# lora.net
KiCad netlist of a schematic drawn in Altium Designer
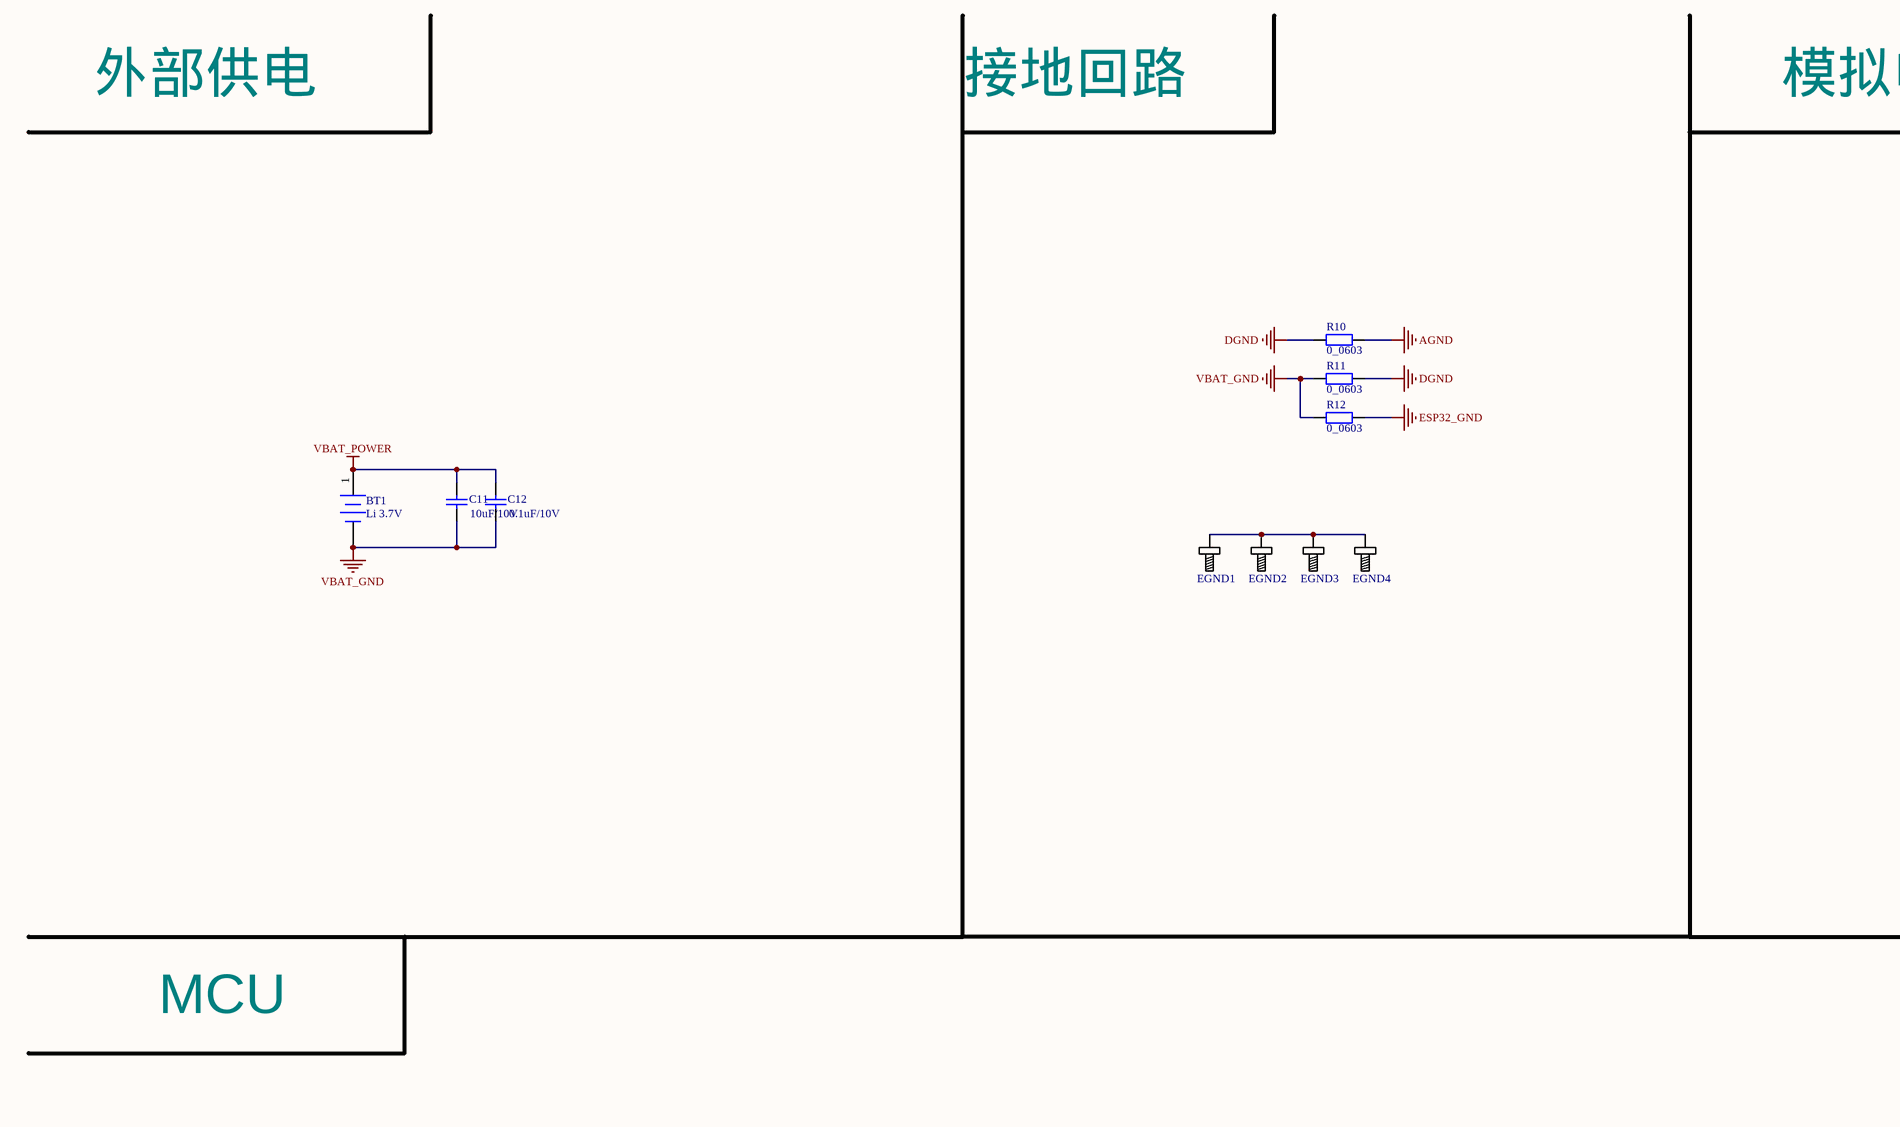
[diagram p0: lora.SchDoc, top left]
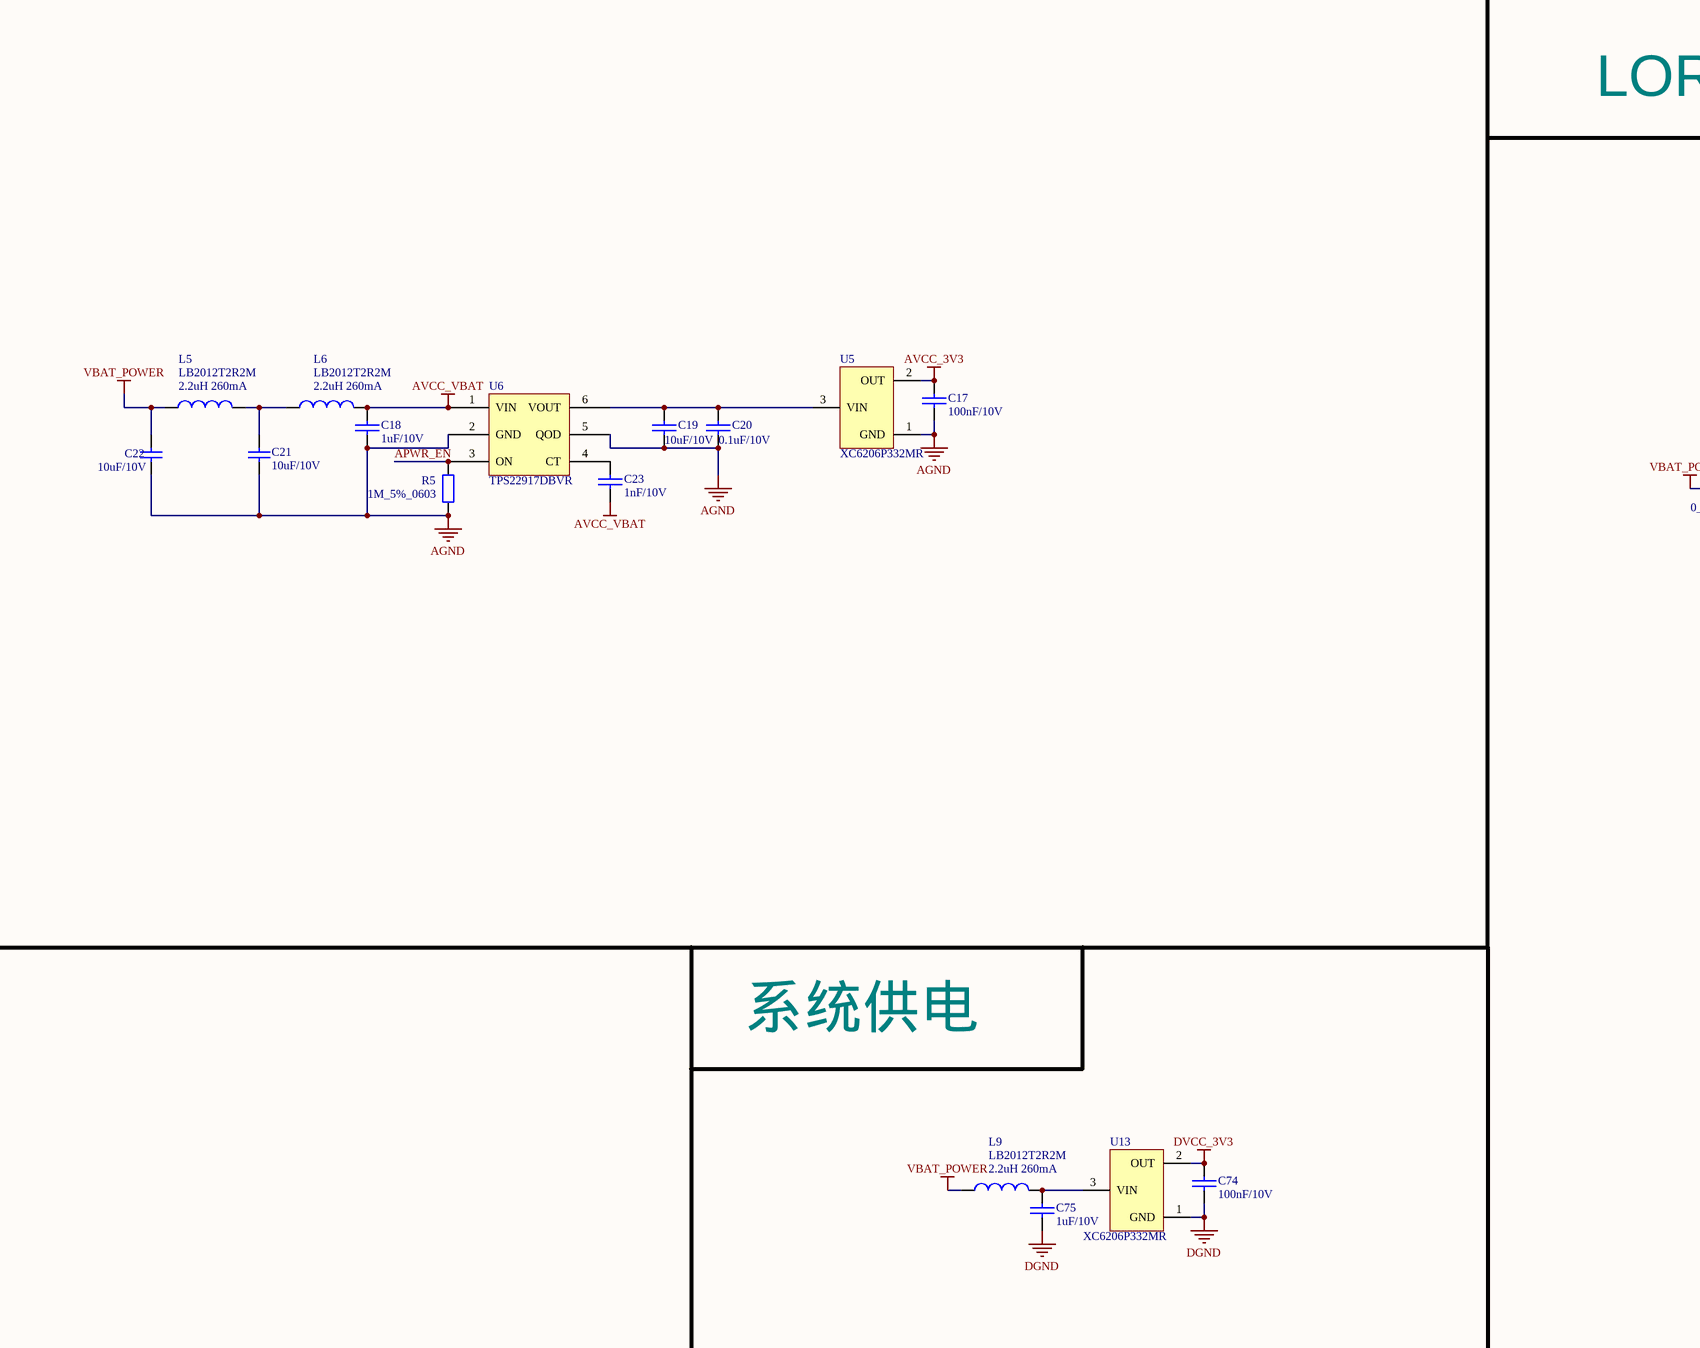
[diagram p1: lora.SchDoc, top middle]
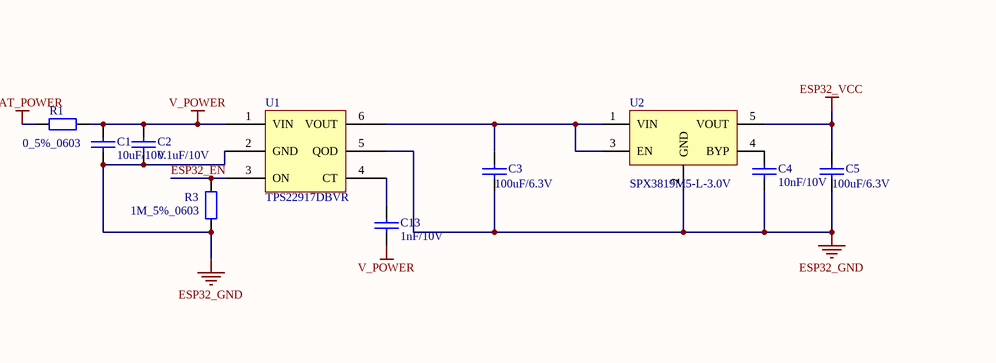
[diagram p2: lora.SchDoc, top right]
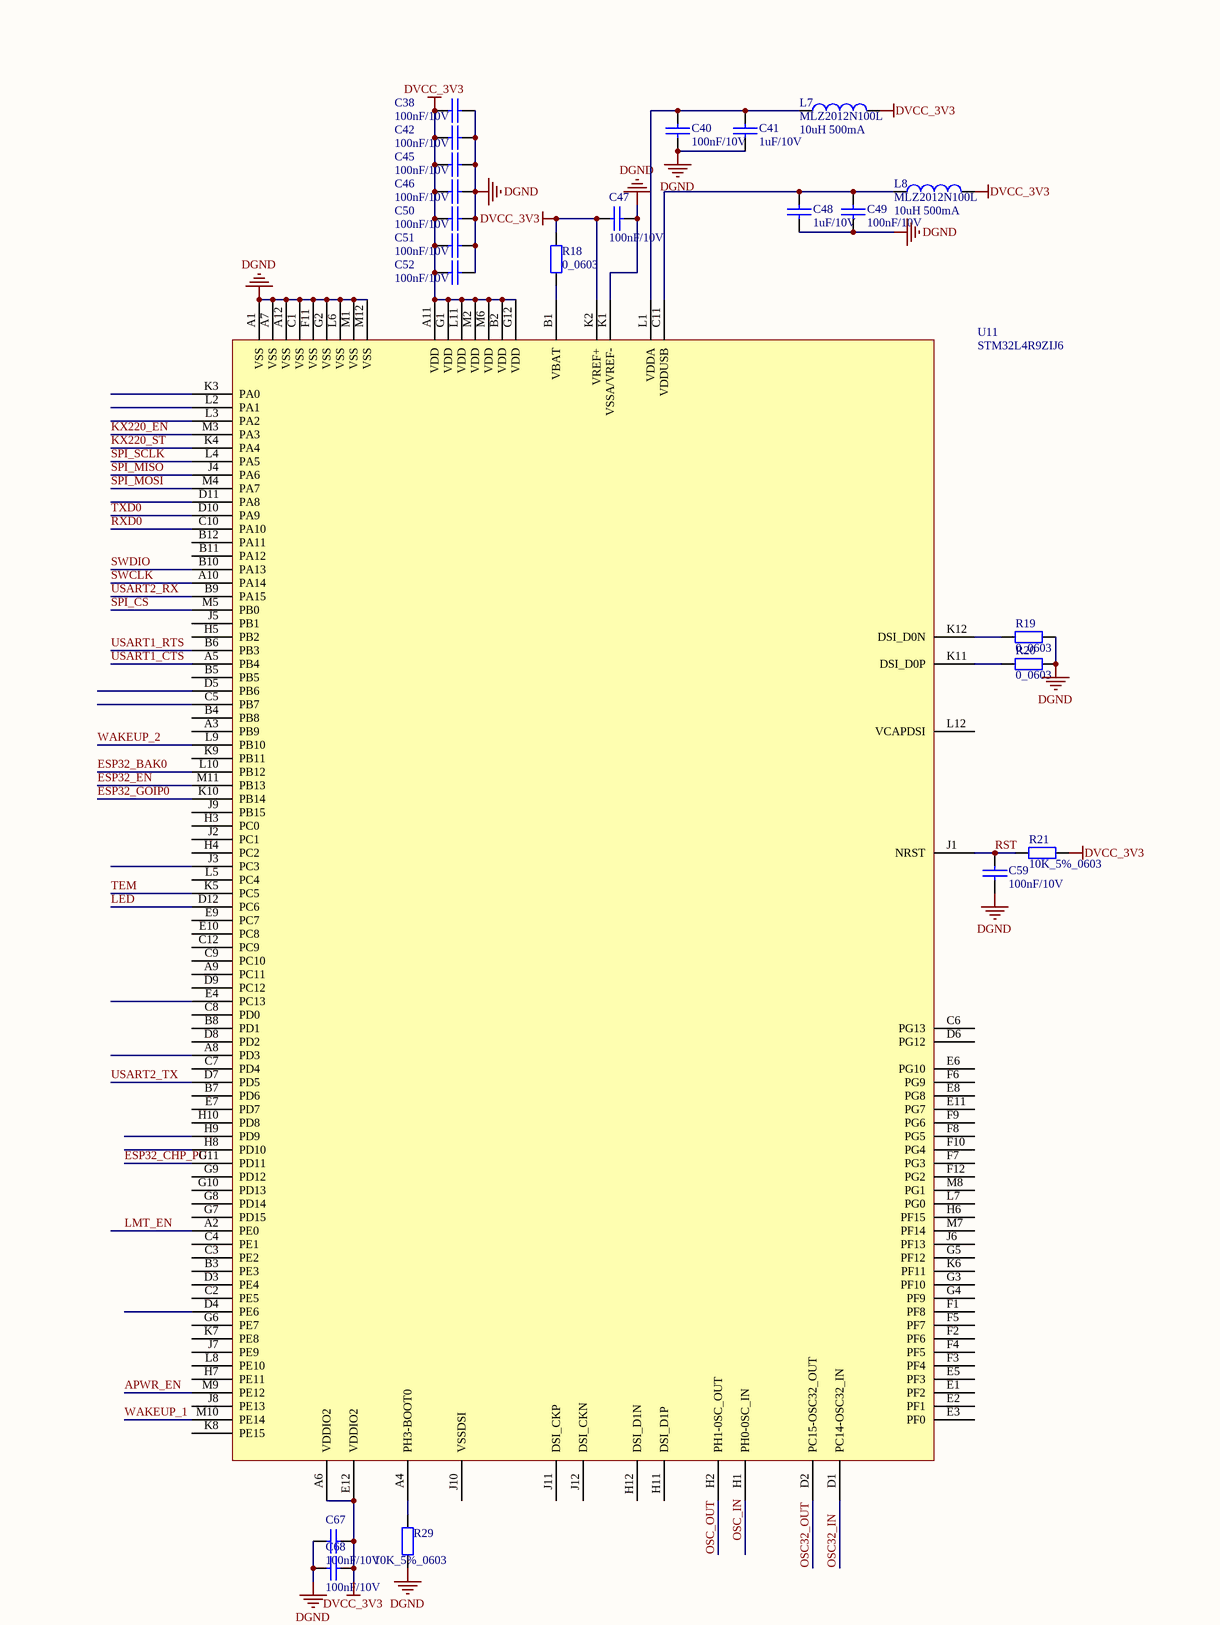
[diagram p3: lora.SchDoc, centre left]
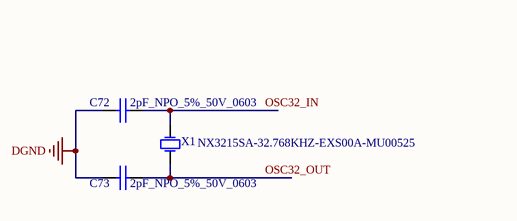
[diagram p4: lora.SchDoc, centre middle]
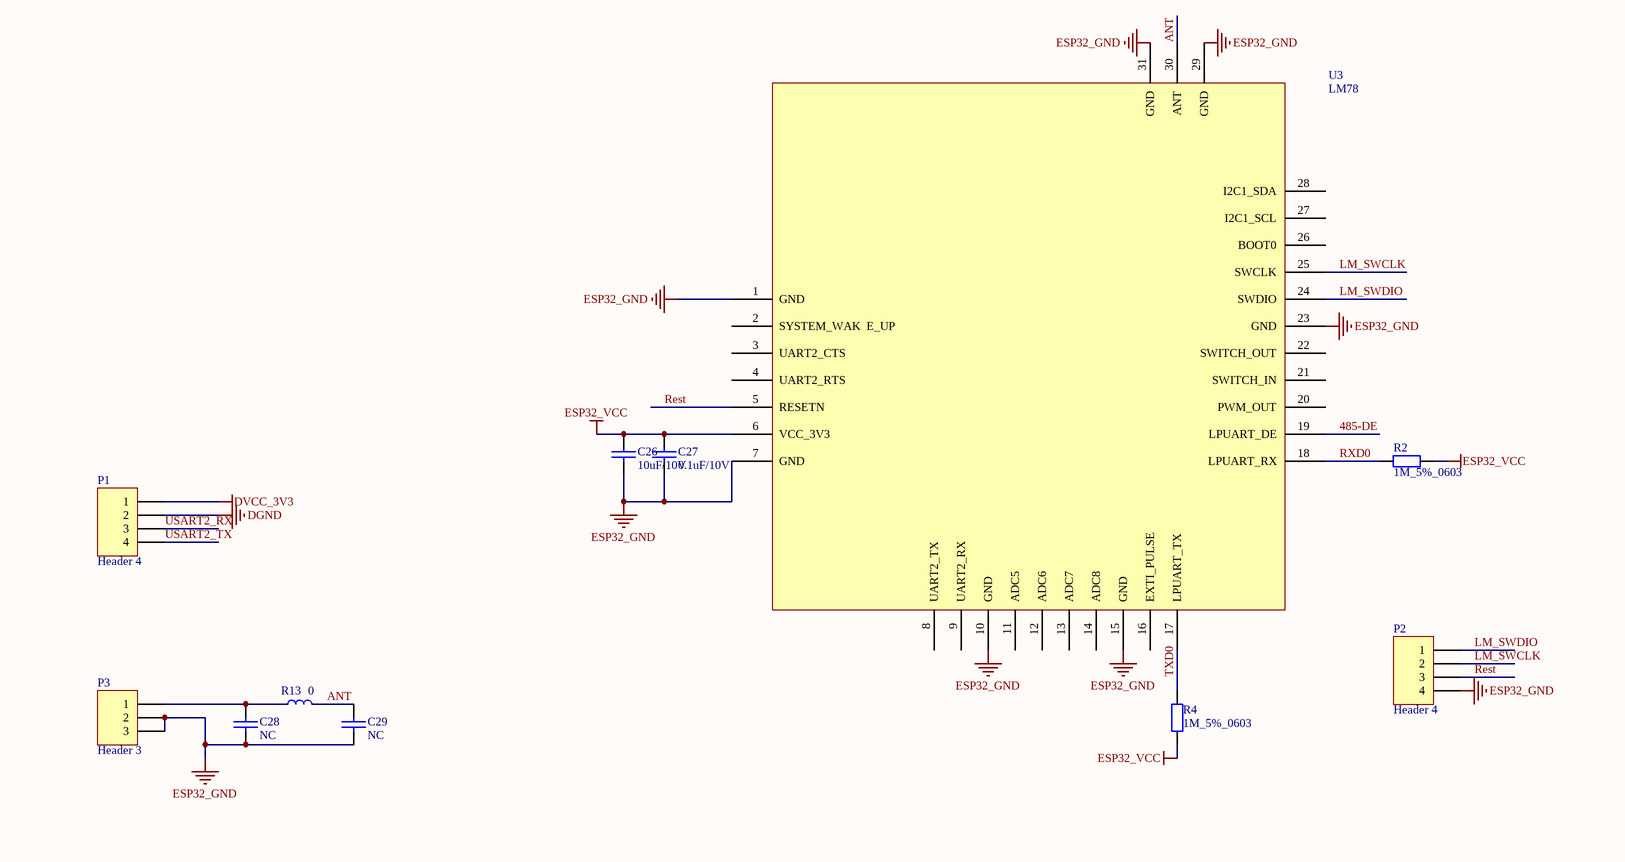
[diagram p5: lora.SchDoc, centre right]
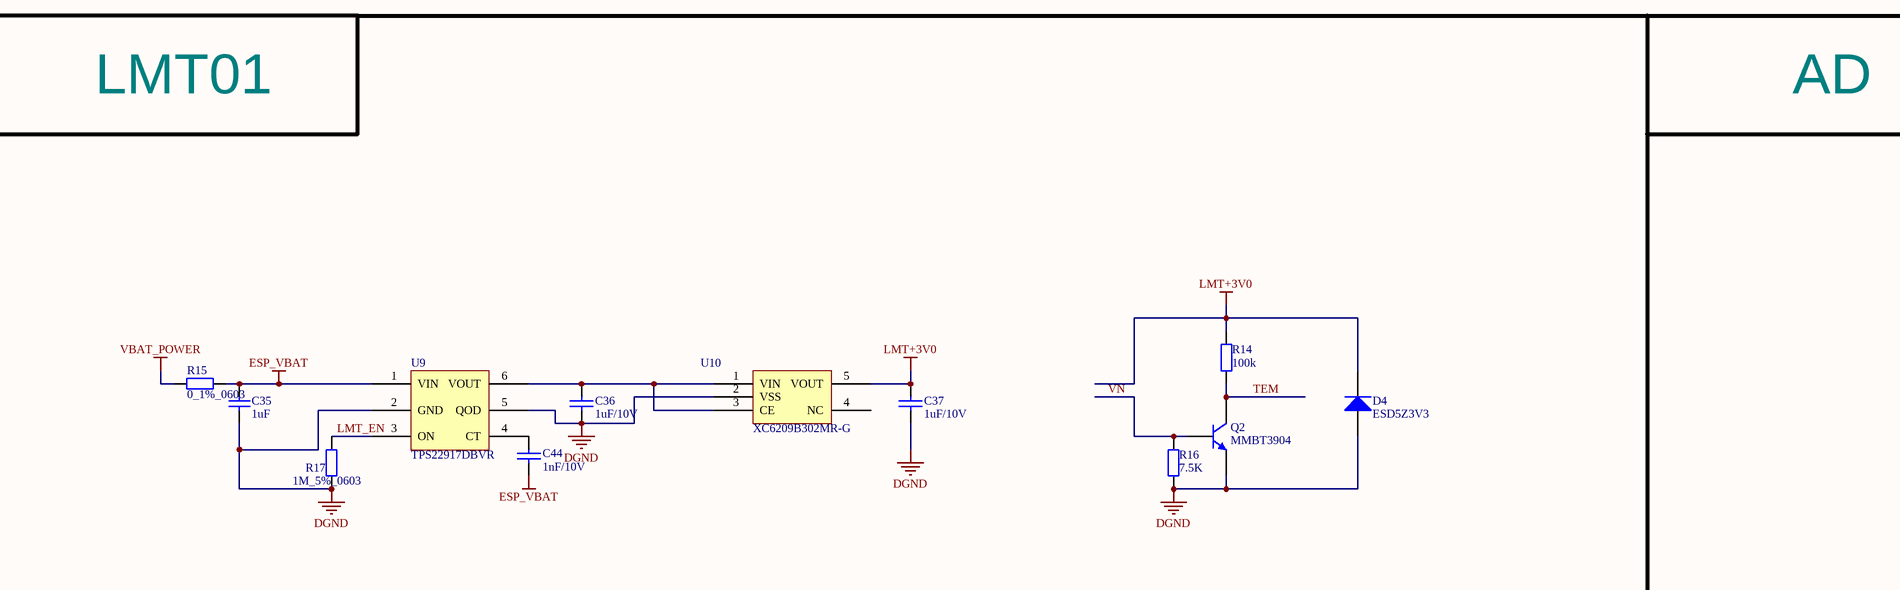
[diagram p6: lora.SchDoc, bottom left]
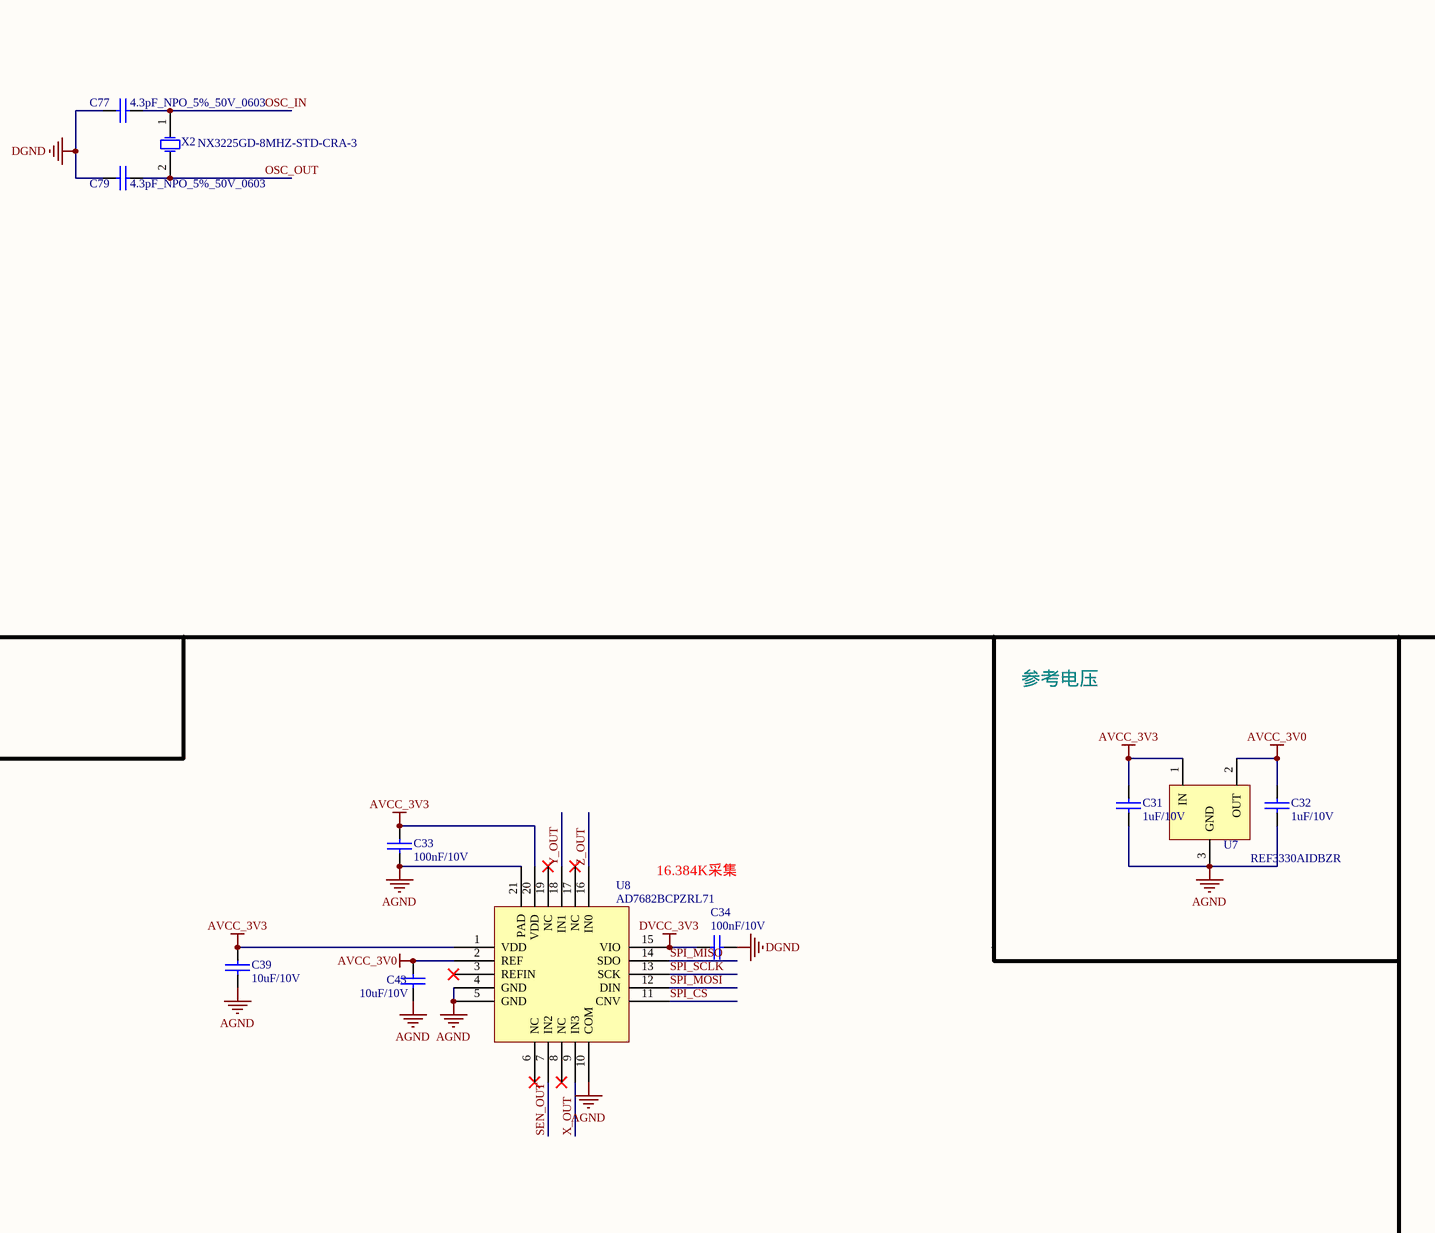
[diagram p7: lora.SchDoc, bottom middle]
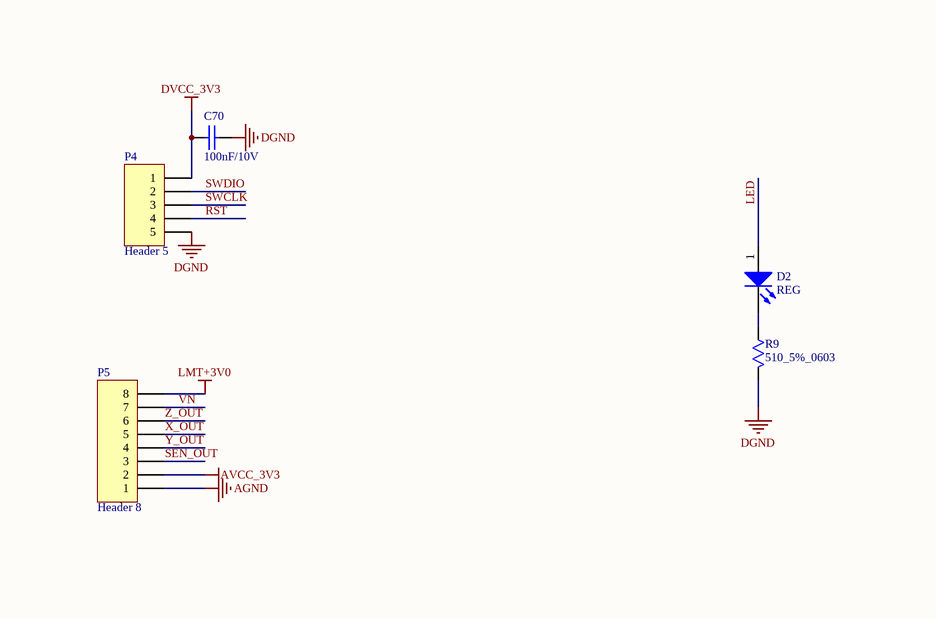
[diagram p8: lora.SchDoc, bottom right]

(export (version "E")
  (design (tool "Eeschema 10.0.6"))
  (components
    (comp (ref "BT1")
      (value "Li 3.7V")
      (footprint "PH2.0-WI-2P")
      (description "能量型锂亚电池")
      (fields (field (name "PUBLISHER") "Altium Limited"))
      (libsource (lib "cjqLIB") (part "Battery"))
    )
    (comp (ref "C1")
      (value "10uF/10V")
      (footprint "0603C")
      (description "10uF_X5R_10%_10V_0603")
      (libsource (lib "*") (part "CAP"))
    )
    (comp (ref "C2")
      (value "0.1uF/10V")
      (footprint "0603C")
      (description "0.1uF_X5R_10%_10V_0603")
      (libsource (lib "*") (part "CAP"))
    )
    (comp (ref "C3")
      (value "100uF/6.3V")
      (footprint "1206C")
      (description "100uF_X5R_20%_6.3V_1206")
      (libsource (lib "*") (part "CAP"))
    )
    (comp (ref "C4")
      (value "10nF/10V")
      (footprint "0603C")
      (description "10nF_X7R_10%_10V_0603")
      (libsource (lib "*") (part "CAP"))
    )
    (comp (ref "C5")
      (value "100uF/6.3V")
      (footprint "1206C")
      (description "100uF_X5R_20%_6.3V_1206")
      (libsource (lib "*") (part "CAP"))
    )
    (comp (ref "C11")
      (value "10uF/10V")
      (footprint "0603C")
      (description "10uF_X5R_10%_10V_0603")
      (fields (field (name "PUBLISHER") "Altium Limited"))
      (libsource (lib "cjqLIB") (part "Cap"))
    )
    (comp (ref "C12")
      (value "0.1uF/10V")
      (footprint "0603C")
      (description "0.1uF_X5R_10%_10V_0603")
      (fields (field (name "PUBLISHER") "Altium Limited"))
      (libsource (lib "cjqLIB") (part "Cap"))
    )
    (comp (ref "C13")
      (value "1nF/10V")
      (footprint "0603C")
      (description "1nF_X7R_10%_10V_0603")
      (libsource (lib "*") (part "CAP"))
    )
    (comp (ref "C17")
      (value "100nF/10V")
      (footprint "0603C")
      (description "100nF_X5R_10%_10V_0603")
      (libsource (lib "*") (part "CAP"))
    )
    (comp (ref "C18")
      (value "1uF/10V")
      (footprint "0603C")
      (description "1uF_X5R_10%_10V_0603")
      (libsource (lib "*") (part "CAP"))
    )
    (comp (ref "C19")
      (value "10uF/10V")
      (footprint "0603C")
      (description "10uF_X5R_10%_10V_0603")
      (libsource (lib "*") (part "CAP"))
    )
    (comp (ref "C20")
      (value "0.1uF/10V")
      (footprint "0603C")
      (description "0.1uF_X5R_10%_10V_0603")
      (libsource (lib "*") (part "CAP"))
    )
    (comp (ref "C21")
      (value "10uF/10V")
      (footprint "0603C")
      (description "10uF_X5R_10%_10V_0603")
      (fields (field (name "PUBLISHER") "Altium Limited"))
      (libsource (lib "cjqLIB") (part "Cap"))
    )
    (comp (ref "C22")
      (value "10uF/10V")
      (footprint "0603C")
      (description "10uF_X5R_10%_10V_0603")
      (fields (field (name "PUBLISHER") "Altium Limited"))
      (libsource (lib "cjqLIB") (part "Cap"))
    )
    (comp (ref "C23")
      (value "1nF/10V")
      (footprint "0603C")
      (description "1nF_X7R_10%_10V_0603")
      (libsource (lib "*") (part "CAP"))
    )
    (comp (ref "C26")
      (value "10uF/10V")
      (footprint "0603C")
      (description "10uF_X5R_10%_10V_0603")
      (libsource (lib "*") (part "CAP"))
    )
    (comp (ref "C27")
      (value "0.1uF/10V")
      (footprint "0603C")
      (description "0.1uF_X5R_10%_10V_0603")
      (libsource (lib "*") (part "CAP"))
    )
    (comp (ref "C28")
      (value "NC")
      (footprint "0603C")
      (description "贴片电容")
      (libsource (lib "Zzhsch") (part "CAP"))
    )
    (comp (ref "C29")
      (value "NC")
      (footprint "0603C")
      (description "贴片电容")
      (libsource (lib "Zzhsch") (part "CAP"))
    )
    (comp (ref "C31")
      (value "1uF/10V")
      (footprint "0603C")
      (description "1uF_X5R_10%_10V_0603")
      (libsource (lib "*") (part "CAP"))
    )
    (comp (ref "C32")
      (value "1uF/10V")
      (footprint "0603C")
      (description "1uF_X5R_10%_10V_0603")
      (libsource (lib "*") (part "CAP"))
    )
    (comp (ref "C33")
      (value "100nF/10V")
      (footprint "0402C")
      (description "100nF_X5R_10%_10V_0603")
      (libsource (lib "*") (part "CAP"))
    )
    (comp (ref "C34")
      (value "100nF/10V")
      (footprint "0603C")
      (description "100nF_X5R_10%_10V_0603")
      (libsource (lib "*") (part "CAP"))
    )
    (comp (ref "C35")
      (value "1uF")
      (footprint "0603C")
      (description "1uF_X5R_10%_10V_0603")
      (fields (field (name "PUBLISHER") "Altium Limited"))
      (libsource (lib "cjqLIB") (part "Cap"))
    )
    (comp (ref "C36")
      (value "1uF/10V")
      (footprint "0603C")
      (description "1uF_X5R_10%_10V_0603")
      (libsource (lib "*") (part "CAP"))
    )
    (comp (ref "C37")
      (value "1uF/10V")
      (footprint "0603C")
      (description "1uF_X5R_10%_10V_0603")
      (libsource (lib "*") (part "CAP"))
    )
    (comp (ref "C38")
      (value "100nF/10V")
      (footprint "0603C")
      (description "100nF_X5R_10%_10V_0603")
      (libsource (lib "*") (part "CAP"))
    )
    (comp (ref "C39")
      (value "10uF/10V")
      (footprint "0402C")
      (description "10uF_X5R_10%_10V_0603")
      (libsource (lib "*") (part "CAP"))
    )
    (comp (ref "C40")
      (value "100nF/10V")
      (footprint "0603C")
      (description "100nF_X5R_10%_10V_0603")
      (libsource (lib "*") (part "CAP"))
    )
    (comp (ref "C41")
      (value "1uF/10V")
      (footprint "0603C")
      (description "1uF_X5R_10%_10V_0603")
      (libsource (lib "*") (part "CAP"))
    )
    (comp (ref "C42")
      (value "100nF/10V")
      (footprint "0603C")
      (description "100nF_X5R_10%_10V_0603")
      (libsource (lib "*") (part "CAP"))
    )
    (comp (ref "C43")
      (value "10uF/10V")
      (footprint "0402C")
      (description "10uF_X5R_10%_10V_0603")
      (libsource (lib "*") (part "CAP"))
    )
    (comp (ref "C44")
      (value "1nF/10V")
      (footprint "0603C")
      (description "1nF_X7R_10%_10V_0603")
      (libsource (lib "*") (part "CAP"))
    )
    (comp (ref "C45")
      (value "100nF/10V")
      (footprint "0603C")
      (description "100nF_X5R_10%_10V_0603")
      (libsource (lib "*") (part "CAP"))
    )
    (comp (ref "C46")
      (value "100nF/10V")
      (footprint "0603C")
      (description "100nF_X5R_10%_10V_0603")
      (libsource (lib "*") (part "CAP"))
    )
    (comp (ref "C47")
      (value "100nF/10V")
      (footprint "0603C")
      (description "100nF_X5R_10%_10V_0603")
      (libsource (lib "*") (part "CAP"))
    )
    (comp (ref "C48")
      (value "1uF/10V")
      (footprint "0603C")
      (description "1uF_X5R_10%_10V_0603")
      (libsource (lib "*") (part "CAP"))
    )
    (comp (ref "C49")
      (value "100nF/10V")
      (footprint "0603C")
      (description "100nF_X5R_10%_10V_0603")
      (libsource (lib "*") (part "CAP"))
    )
    (comp (ref "C50")
      (value "100nF/10V")
      (footprint "0603C")
      (description "100nF_X5R_10%_10V_0603")
      (libsource (lib "*") (part "CAP"))
    )
    (comp (ref "C51")
      (value "100nF/10V")
      (footprint "0603C")
      (description "100nF_X5R_10%_10V_0603")
      (libsource (lib "*") (part "CAP"))
    )
    (comp (ref "C52")
      (value "100nF/10V")
      (footprint "0603C")
      (description "100nF_X5R_10%_10V_0603")
      (libsource (lib "*") (part "CAP"))
    )
    (comp (ref "C59")
      (value "100nF/10V")
      (footprint "0603C")
      (description "100nF_X5R_10%_10V_0603")
      (libsource (lib "*") (part "CAP"))
    )
    (comp (ref "C67")
      (value "100nF/10V")
      (footprint "0603C")
      (description "100nF_X5R_10%_10V_0603")
      (libsource (lib "*") (part "CAP"))
    )
    (comp (ref "C68")
      (value "100nF/10V")
      (footprint "0603C")
      (description "100nF_X5R_10%_10V_0603")
      (libsource (lib "*") (part "CAP"))
    )
    (comp (ref "C70")
      (value "100nF/10V")
      (footprint "0603C")
      (description "100nF_X5R_10%_10V_0603")
      (libsource (lib "*") (part "CAP"))
    )
    (comp (ref "C72") (value "2pF_NPO_5%_50V_0603") (footprint "0603C") (libsource (lib "*") (part "CAP")))
    (comp (ref "C73") (value "2pF_NPO_5%_50V_0603") (footprint "0603C") (libsource (lib "*") (part "CAP")))
    (comp (ref "C74")
      (value "100nF/10V")
      (footprint "0603C")
      (description "100nF_X5R_10%_10V_0603")
      (libsource (lib "*") (part "CAP"))
    )
    (comp (ref "C75")
      (value "1uF/10V")
      (footprint "0603C")
      (description "1uF_X5R_10%_10V_0603")
      (libsource (lib "*") (part "CAP"))
    )
    (comp (ref "C77") (value "4.3pF_NPO_5%_50V_0603") (footprint "0603C") (libsource (lib "*") (part "CAP")))
    (comp (ref "C79") (value "4.3pF_NPO_5%_50V_0603") (footprint "0603C") (libsource (lib "*") (part "CAP")))
    (comp (ref "D2")
      (value "REG")
      (footprint "LED 0805B")
      (description "贴片LED 蓝灯1206")
      (fields (field (name "PUBLISHER") "Altium Limited"))
      (libsource (lib "cjqLIB") (part "LED0"))
    )
    (comp (ref "D4")
      (value "ESD5Z3V3")
      (footprint "SOD-523")
      (description "ESD二极管")
      (fields (field (name "PUBLISHER") "Altium Limited"))
      (libsource (lib "Miscellaneous Devices") (part "Diode"))
    )
    (comp (ref "EGND1")
      (value "EGND")
      (footprint "M2.5x4")
      (description "M3铜柱，长：4mm")
      (libsource (lib "Zzhsch") (part "M3x4+6_L"))
    )
    (comp (ref "EGND2")
      (value "EGND")
      (footprint "M2.5x4")
      (description "M3铜柱，长：4mm")
      (libsource (lib "Zzhsch") (part "M3x4+6_L"))
    )
    (comp (ref "EGND3")
      (value "EGND")
      (footprint "M2.5x4")
      (description "M3铜柱，长：4mm")
      (libsource (lib "Zzhsch") (part "M3x4+6_L"))
    )
    (comp (ref "EGND4")
      (value "EGND")
      (footprint "M2.5x4")
      (description "M3铜柱，长：4mm")
      (libsource (lib "Zzhsch") (part "M3x4+6_L"))
    )
    (comp (ref "L5")
      (value "LB2012T2R2M")
      (footprint "L 0805")
      (description "固定电感器0805")
      (fields (field (name "ALTIUM_VALUE") "2.2uH 260mA") (field (name "PUBLISHER") "Altium Limited"))
      (libsource (lib "Miscellaneous Devices") (part "Inductor"))
    )
    (comp (ref "L6")
      (value "LB2012T2R2M")
      (footprint "L 0805")
      (description "Taiyo Yuden固定电感器0805")
      (fields (field (name "ALTIUM_VALUE") "2.2uH 260mA") (field (name "PUBLISHER") "Altium Limited"))
      (libsource (lib "Miscellaneous Devices") (part "Inductor"))
    )
    (comp (ref "L7")
      (value "MLZ2012N100L")
      (footprint "L 0805")
      (description "TDK固定电感器10uH")
      (fields (field (name "ALTIUM_VALUE") "10uH 500mA") (field (name "PUBLISHER") "Altium Limited"))
      (libsource (lib "Miscellaneous Devices") (part "Inductor"))
    )
    (comp (ref "L8")
      (value "MLZ2012N100L")
      (footprint "L 0805")
      (description "TDK固定电感器10uH")
      (fields (field (name "ALTIUM_VALUE") "10uH 500mA") (field (name "PUBLISHER") "Altium Limited"))
      (libsource (lib "Miscellaneous Devices") (part "Inductor"))
    )
    (comp (ref "L9")
      (value "LB2012T2R2M")
      (footprint "L 0805")
      (description "Taiyo Yuden固定电感器0805")
      (fields (field (name "ALTIUM_VALUE") "2.2uH 260mA") (field (name "PUBLISHER") "Altium Limited"))
      (libsource (lib "Miscellaneous Devices") (part "Inductor"))
    )
    (comp (ref "P1")
      (value "Header 4")
      (footprint "HDR2.0-LI-4P")
      (description "Header, 4-Pin")
      (fields (field (name "PUBLISHER") "Altium Limited"))
      (libsource (lib "Miscellaneous Connectors") (part "Header 4"))
    )
    (comp (ref "P2")
      (value "Header 4")
      (footprint "HDR2.0-LI-4P")
      (description "Header, 4-Pin")
      (fields (field (name "PUBLISHER") "Altium Limited"))
      (libsource (lib "Miscellaneous Connectors") (part "Header 4"))
    )
    (comp (ref "P3")
      (value "Header 3")
      (footprint "SMA-KE")
      (description "SMA 偏脚射频天线座 1.6mm")
      (fields (field (name "PUBLISHER") "Altium Limited"))
      (libsource (lib "Miscellaneous Connectors") (part "Header 3"))
    )
    (comp (ref "P4")
      (value "Header 5")
      (footprint "HDR2.0-LI-5P")
      (description "Header, 5-Pin")
      (fields (field (name "PUBLISHER") "Altium Limited"))
      (libsource (lib "Miscellaneous Connectors") (part "Header 5"))
    )
    (comp (ref "P5")
      (value "Header 8")
      (footprint "FPC1.0-2H-WS-8P")
      (description "Header, 8-Pin")
      (fields (field (name "PUBLISHER") "Altium Limited"))
      (libsource (lib "Miscellaneous Connectors") (part "Header 8"))
    )
    (comp (ref "Q2")
      (value "MMBT3904")
      (footprint "SOT23-3N")
      (description "三极管_NPN")
      (fields (field (name "PUBLISHER") "Altium Limited"))
      (libsource (lib "Miscellaneous Devices") (part "2N3904"))
    )
    (comp (ref "R1")
      (value "0_5%_0603")
      (footprint "0603R")
      (description "1M_5%_0603")
      (fields (field (name "PUBLISHER") "Altium Limited"))
      (libsource (lib "") (part "Res2_3"))
    )
    (comp (ref "R2")
      (value "1M_5%_0603")
      (footprint "0603R")
      (fields (field (name "PUBLISHER") "Altium Limited"))
      (libsource (lib "Miscellaneous Devices") (part "Res2"))
    )
    (comp (ref "R3")
      (value "1M_5%_0603")
      (footprint "0603R")
      (fields (field (name "PUBLISHER") "Altium Limited"))
      (libsource (lib "") (part "Res2_1"))
    )
    (comp (ref "R4")
      (value "1M_5%_0603")
      (footprint "0603R")
      (fields (field (name "PUBLISHER") "Altium Limited"))
      (libsource (lib "") (part "Res2_2"))
    )
    (comp (ref "R5")
      (value "1M_5%_0603")
      (footprint "0603R")
      (fields (field (name "PUBLISHER") "Altium Limited"))
      (libsource (lib "") (part "Res2_1"))
    )
    (comp (ref "R9") (value "510_5%_0603") (footprint "0603R") (libsource (lib "YT1_SCH_99SE") (part "RES")))
    (comp (ref "R10")
      (value "0_0603")
      (footprint "0603R")
      (fields (field (name "PUBLISHER") "Altium Limited"))
      (libsource (lib "Miscellaneous Devices") (part "Res2"))
    )
    (comp (ref "R11")
      (value "0_0603")
      (footprint "0603R")
      (fields (field (name "PUBLISHER") "Altium Limited"))
      (libsource (lib "Miscellaneous Devices") (part "Res2"))
    )
    (comp (ref "R12")
      (value "0_0603")
      (footprint "0603R")
      (fields (field (name "PUBLISHER") "Altium Limited"))
      (libsource (lib "Miscellaneous Devices") (part "Res2"))
    )
    (comp (ref "R13") (value "0") (footprint "0603R") (libsource (lib "Zzhsch") (part "L0.2")))
    (comp (ref "R14")
      (value "100k")
      (footprint "0603R")
      (description "100K_1%_0603")
      (fields (field (name "PUBLISHER") "Altium Limited"))
      (libsource (lib "") (part "Res2_1"))
    )
    (comp (ref "R15")
      (value "0_1%_0603")
      (footprint "0603R")
      (fields (field (name "PUBLISHER") "Altium Limited"))
      (libsource (lib "LQC7.820.2632") (part "Res2"))
    )
    (comp (ref "R16")
      (value "7.5K")
      (footprint "0603R")
      (description "7.5K_1%_0603")
      (fields (field (name "PUBLISHER") "Altium Limited"))
      (libsource (lib "") (part "Res2_1"))
    )
    (comp (ref "R17")
      (value "1M_5%_0603")
      (footprint "0603R")
      (fields (field (name "PUBLISHER") "Altium Limited"))
      (libsource (lib "") (part "Res2_1"))
    )
    (comp (ref "R18")
      (value "0_0603")
      (footprint "0603R")
      (description "贴片电阻0603")
      (fields (field (name "PUBLISHER") "Altium Limited"))
      (libsource (lib "") (part "Res2_1"))
    )
    (comp (ref "R19")
      (value "0_0603")
      (footprint "0603R")
      (description "贴片电阻0603")
      (fields (field (name "PUBLISHER") "Altium Limited"))
      (libsource (lib "") (part "Res2_3"))
    )
    (comp (ref "R20")
      (value "0_0603")
      (footprint "0603R")
      (description "贴片电阻0603")
      (fields (field (name "PUBLISHER") "Altium Limited"))
      (libsource (lib "") (part "Res2_3"))
    )
    (comp (ref "R21")
      (value "10K_5%_0603")
      (footprint "0603R")
      (description "贴片电阻0603")
      (fields (field (name "PUBLISHER") "Altium Limited"))
      (libsource (lib "Miscellaneous Devices") (part "Res2"))
    )
    (comp (ref "R29")
      (value "10K_5%_0603")
      (footprint "0603R")
      (description "贴片电阻0603")
      (fields (field (name "PUBLISHER") "Altium Limited"))
      (libsource (lib "") (part "Res2_2"))
    )
    (comp (ref "U1")
      (value "TPS22917DBVR")
      (footprint "SOT23-6")
      (description "1V 至 5.5V、2A、80mΩ 超低泄漏负载开关")
      (libsource (lib "君岳伟信") (part "TPS22917DBVR"))
    )
    (comp (ref "U2")
      (value "SPX3819M5-L-3.0V")
      (footprint "SOT23-5")
      (description "低压差700mVLDO SOT23-5")
      (libsource (lib "cjqLIB") (part "CAT6219"))
    )
    (comp (ref "U3")
      (value "LM78")
      (footprint "LM78")
      (description "Lora模块 LoRaWAN LM78 天津中科智城网络技术有限公司 LM78")
      (libsource (lib "Schlib1") (part "LM78"))
    )
    (comp (ref "U5")
      (value "XC6206P332MR")
      (footprint "SOT23-3N")
      (description "低压差线性稳压(LDO)_SOT23")
      (libsource (lib "LHchiplibrary") (part "XC6206P282R"))
    )
    (comp (ref "U6")
      (value "TPS22917DBVR")
      (footprint "SOT23-6")
      (description "1V 至 5.5V、2A、80mΩ 超低泄漏负载开关")
      (libsource (lib "君岳伟信") (part "TPS22917DBVR"))
    )
    (comp (ref "U7")
      (value "REF3330AIDBZR")
      (footprint "SOT23-3N")
      (description "参考电压 3V 5mA")
      (libsource (lib "cjqLIB") (part "REF3025"))
    )
    (comp (ref "U8")
      (value "AD7682BCPZRL71")
      (footprint "LFCSP-20")
      (description "ADI 16位 250KSPS PulSAR数模转换器")
      (libsource (lib "君岳伟信") (part "AD7682BCPZRL71"))
    )
    (comp (ref "U9")
      (value "TPS22917DBVR")
      (footprint "SOT23-6")
      (description "1V 至 5.5V、2A、80mΩ 超低泄漏负载开关")
      (libsource (lib "君岳伟信") (part "TPS22917DBVR"))
    )
    (comp (ref "U10")
      (value "XC6209B302MR-G")
      (footprint "SOT23-5")
      (description "低压差线性稳压(LDO)")
      (libsource (lib "高防护温度传感器") (part "XC6209B332-G"))
    )
    (comp (ref "U11")
      (value "STM32L4R9ZIJ6")
      (footprint "UFBGA144")
      (libsource (lib "STM32") (part "Component_1"))
    )
    (comp (ref "U13")
      (value "XC6206P332MR")
      (footprint "SOT23-3N")
      (description "贴片集成电路")
      (libsource (lib "LHchiplibrary") (part "XC6206P282R"))
    )
    (comp (ref "X1")
      (value "NX3215SA-32.768KHZ-EXS00A-MU00525")
      (footprint "OSC 3215-2P")
      (description "无源晶振 32.768KHz 10ppm")
      (libsource (lib "SCH_Oscillator") (part "XTAL_5032_2P"))
    )
    (comp (ref "X2")
      (value "NX3225GD-8MHZ-STD-CRA-3")
      (footprint "OSC 3225-2P")
      (description "NDK无源晶振 8MHz")
      (fields (field (name "PUBLISHER") "Altium Limited"))
      (libsource (lib "MB963_1") (part "XTAL"))
    )
  )
  (nets
    (net (code "1") (name "/485-DE") (class "Default")
      (node (ref "U3") (pin "19") (pinfunction "LPUART_DE_19") (pintype "passive"))
    )
    (net (code "2") (name "/ANT") (class "Default")
      (node (ref "C29") (pin "1") (pintype "passive"))
      (node (ref "R13") (pin "1") (pinfunction "1_1") (pintype "passive"))
      (node (ref "U3") (pin "30") (pinfunction "ANT_30") (pintype "passive"))
    )
    (net (code "3") (name "/APWR_EN") (class "Default")
      (node (ref "R5") (pin "1") (pinfunction "1_1") (pintype "passive"))
      (node (ref "U11") (pin "M9") (pinfunction "PE12_M9") (pintype "passive"))
      (node (ref "U6") (pin "3") (pinfunction "ON_3") (pintype "passive"))
    )
    (net (code "4") (name "/ESP32_BAK0") (class "Default")
      (node (ref "U11") (pin "L10") (pinfunction "PB12_L10") (pintype "passive"))
    )
    (net (code "5") (name "/ESP32_CHP_PU") (class "Default")
      (node (ref "U11") (pin "G11") (pinfunction "PD11_G11") (pintype "passive"))
    )
    (net (code "6") (name "/ESP32_EN") (class "Default")
      (node (ref "R3") (pin "1") (pinfunction "1_1") (pintype "passive"))
      (node (ref "U1") (pin "3") (pinfunction "ON_3") (pintype "passive"))
      (node (ref "U11") (pin "M11") (pinfunction "PB13_M11") (pintype "passive"))
    )
    (net (code "7") (name "/ESP32_GOIP0") (class "Default")
      (node (ref "U11") (pin "K10") (pinfunction "PB14_K10") (pintype "passive"))
    )
    (net (code "8") (name "/KX220_EN") (class "Default")
      (node (ref "U11") (pin "M3") (pinfunction "PA3_M3") (pintype "passive"))
    )
    (net (code "9") (name "/KX220_ST") (class "Default")
      (node (ref "U11") (pin "K4") (pinfunction "PA4_K4") (pintype "passive"))
    )
    (net (code "10") (name "/LED") (class "Default")
      (node (ref "D2") (pin "1") (pinfunction "A_1") (pintype "passive"))
      (node (ref "U11") (pin "D12") (pinfunction "PC6_D12") (pintype "passive"))
    )
    (net (code "11") (name "/LMT_EN") (class "Default")
      (node (ref "R17") (pin "1") (pinfunction "1_1") (pintype "passive"))
      (node (ref "U11") (pin "A2") (pinfunction "PE0_A2") (pintype "passive"))
      (node (ref "U9") (pin "3") (pinfunction "ON_3") (pintype "passive"))
    )
    (net (code "12") (name "/LM_SWCLK") (class "Default")
      (node (ref "P2") (pin "2") (pinfunction "2_2") (pintype "passive"))
      (node (ref "U3") (pin "25") (pinfunction "SWCLK_25") (pintype "passive"))
    )
    (net (code "13") (name "/LM_SWDIO") (class "Default")
      (node (ref "P2") (pin "1") (pinfunction "1_1") (pintype "passive"))
      (node (ref "U3") (pin "24") (pinfunction "SWDIO_24") (pintype "passive"))
    )
    (net (code "14") (name "/OSC32_IN") (class "Default")
      (node (ref "C72") (pin "1") (pinfunction "1_1") (pintype "passive"))
      (node (ref "U11") (pin "D1") (pinfunction "PC14-OSC32_IN_D1") (pintype "passive"))
      (node (ref "X1") (pin "1") (pinfunction "OSC1_1") (pintype "passive"))
    )
    (net (code "15") (name "/OSC32_OUT") (class "Default")
      (node (ref "C73") (pin "1") (pinfunction "1_1") (pintype "passive"))
      (node (ref "U11") (pin "D2") (pinfunction "PC15-OSC32_OUT_D2") (pintype "passive"))
      (node (ref "X1") (pin "2") (pinfunction "OSC2_2") (pintype "passive"))
    )
    (net (code "16") (name "/OSC_IN") (class "Default")
      (node (ref "C77") (pin "1") (pinfunction "1_1") (pintype "passive"))
      (node (ref "U11") (pin "H1") (pinfunction "PH0-0SC_IN_H1") (pintype "passive"))
      (node (ref "X2") (pin "1") (pinfunction "OSC1_1") (pintype "passive"))
    )
    (net (code "17") (name "/OSC_OUT") (class "Default")
      (node (ref "C79") (pin "1") (pinfunction "1_1") (pintype "passive"))
      (node (ref "U11") (pin "H2") (pinfunction "PH1-0SC_OUT_H2") (pintype "passive"))
      (node (ref "X2") (pin "2") (pinfunction "OSC2_2") (pintype "passive"))
    )
    (net (code "18") (name "/RST") (class "Default")
      (node (ref "C59") (pin "2") (pinfunction "2_2") (pintype "passive"))
      (node (ref "P4") (pin "4") (pinfunction "4_4") (pintype "passive"))
      (node (ref "R21") (pin "2") (pinfunction "2_2") (pintype "passive"))
      (node (ref "U11") (pin "J1") (pinfunction "NRST_J1") (pintype "passive"))
    )
    (net (code "19") (name "/RXD0") (class "Default")
      (node (ref "R2") (pin "2") (pinfunction "2_2") (pintype "passive"))
      (node (ref "U11") (pin "C10") (pinfunction "PA10_C10") (pintype "passive"))
      (node (ref "U3") (pin "18") (pinfunction "LPUART_RX_18") (pintype "passive"))
    )
    (net (code "20") (name "/Rest") (class "Default")
      (node (ref "P2") (pin "3") (pinfunction "3_3") (pintype "passive"))
      (node (ref "U3") (pin "5") (pinfunction "RESETN_5") (pintype "passive"))
    )
    (net (code "21") (name "/SEN_OUT") (class "Default")
      (node (ref "P5") (pin "3") (pinfunction "3_3") (pintype "passive"))
      (node (ref "U8") (pin "7") (pinfunction "IN2_7") (pintype "passive"))
    )
    (net (code "22") (name "/SPI_CS") (class "Default")
      (node (ref "U11") (pin "M5") (pinfunction "PB0_M5") (pintype "passive"))
      (node (ref "U8") (pin "11") (pinfunction "CNV_11") (pintype "passive"))
    )
    (net (code "23") (name "/SPI_MISO") (class "Default")
      (node (ref "U11") (pin "J4") (pinfunction "PA6_J4") (pintype "passive"))
      (node (ref "U8") (pin "14") (pinfunction "SDO_14") (pintype "passive"))
    )
    (net (code "24") (name "/SPI_MOSI") (class "Default")
      (node (ref "U11") (pin "M4") (pinfunction "PA7_M4") (pintype "passive"))
      (node (ref "U8") (pin "12") (pinfunction "DIN_12") (pintype "passive"))
    )
    (net (code "25") (name "/SPI_SCLK") (class "Default")
      (node (ref "U11") (pin "L4") (pinfunction "PA5_L4") (pintype "passive"))
      (node (ref "U8") (pin "13") (pinfunction "SCK_13") (pintype "passive"))
    )
    (net (code "26") (name "/SWCLK") (class "Default")
      (node (ref "P4") (pin "3") (pinfunction "3_3") (pintype "passive"))
      (node (ref "U11") (pin "A10") (pinfunction "PA14_A10") (pintype "passive"))
    )
    (net (code "27") (name "/SWDIO") (class "Default")
      (node (ref "P4") (pin "2") (pinfunction "2_2") (pintype "passive"))
      (node (ref "U11") (pin "B10") (pinfunction "PA13_B10") (pintype "passive"))
    )
    (net (code "28") (name "/TEM") (class "Default")
      (node (ref "Q2") (pin "3") (pinfunction "C_3") (pintype "passive"))
      (node (ref "R14") (pin "2") (pinfunction "2_2") (pintype "passive"))
      (node (ref "U11") (pin "K5") (pinfunction "PC5_K5") (pintype "passive"))
    )
    (net (code "29") (name "/TXD0") (class "Default")
      (node (ref "R4") (pin "2") (pinfunction "2_2") (pintype "passive"))
      (node (ref "U11") (pin "D10") (pinfunction "PA9_D10") (pintype "passive"))
      (node (ref "U3") (pin "17") (pinfunction "LPUART_TX_17") (pintype "passive"))
    )
    (net (code "30") (name "/USART1_CTS") (class "Default")
      (node (ref "U11") (pin "A5") (pinfunction "PB4_A5") (pintype "passive"))
    )
    (net (code "31") (name "/USART1_RTS") (class "Default")
      (node (ref "U11") (pin "B6") (pinfunction "PB3_B6") (pintype "passive"))
    )
    (net (code "32") (name "/USART2_RX") (class "Default")
      (node (ref "P1") (pin "3") (pinfunction "3_3") (pintype "passive"))
      (node (ref "U11") (pin "B9") (pinfunction "PA15_B9") (pintype "passive"))
    )
    (net (code "33") (name "/USART2_TX") (class "Default")
      (node (ref "P1") (pin "4") (pinfunction "4_4") (pintype "passive"))
      (node (ref "U11") (pin "D7") (pinfunction "PD5_D7") (pintype "passive"))
    )
    (net (code "34") (name "/VN") (class "Default")
      (node (ref "P5") (pin "7") (pinfunction "7_7") (pintype "passive"))
      (node (ref "Q2") (pin "1") (pinfunction "B_1") (pintype "passive"))
      (node (ref "R16") (pin "1") (pinfunction "1_1") (pintype "passive"))
    )
    (net (code "35") (name "/WAKEUP_1") (class "Default")
      (node (ref "U11") (pin "M10") (pinfunction "PE14_M10") (pintype "passive"))
    )
    (net (code "36") (name "/WAKEUP_2") (class "Default")
      (node (ref "U11") (pin "L9") (pinfunction "PB10_L9") (pintype "passive"))
    )
    (net (code "37") (name "/X_OUT") (class "Default")
      (node (ref "P5") (pin "5") (pinfunction "5_5") (pintype "passive"))
      (node (ref "U8") (pin "9") (pinfunction "IN3_9") (pintype "passive"))
    )
    (net (code "38") (name "/Y_OUT") (class "Default")
      (node (ref "P5") (pin "4") (pinfunction "4_4") (pintype "passive"))
      (node (ref "U8") (pin "18") (pinfunction "IN1_18") (pintype "passive"))
    )
    (net (code "39") (name "/Z_OUT") (class "Default")
      (node (ref "P5") (pin "6") (pinfunction "6_6") (pintype "passive"))
      (node (ref "U8") (pin "16") (pinfunction "IN0_16") (pintype "passive"))
    )
    (net (code "40") (name "AGND") (class "Default")
      (node (ref "C17") (pin "2") (pinfunction "2_2") (pintype "passive"))
      (node (ref "C18") (pin "2") (pinfunction "2_2") (pintype "passive"))
      (node (ref "C19") (pin "2") (pinfunction "2_2") (pintype "passive"))
      (node (ref "C20") (pin "2") (pinfunction "2_2") (pintype "passive"))
      (node (ref "C21") (pin "2") (pinfunction "2_2") (pintype "passive"))
      (node (ref "C22") (pin "2") (pinfunction "2_2") (pintype "passive"))
      (node (ref "C31") (pin "2") (pinfunction "2_2") (pintype "passive"))
      (node (ref "C32") (pin "2") (pinfunction "2_2") (pintype "passive"))
      (node (ref "C33") (pin "2") (pinfunction "2_2") (pintype "passive"))
      (node (ref "C39") (pin "2") (pinfunction "2_2") (pintype "passive"))
      (node (ref "C43") (pin "2") (pinfunction "2_2") (pintype "passive"))
      (node (ref "P5") (pin "1") (pinfunction "1_1") (pintype "passive"))
      (node (ref "R10") (pin "1") (pinfunction "1_1") (pintype "passive"))
      (node (ref "R5") (pin "2") (pinfunction "2_2") (pintype "passive"))
      (node (ref "U5") (pin "1") (pinfunction "GND_1") (pintype "passive"))
      (node (ref "U6") (pin "2") (pinfunction "GND_2") (pintype "passive"))
      (node (ref "U6") (pin "5") (pinfunction "QOD_5") (pintype "passive"))
      (node (ref "U7") (pin "3") (pinfunction "GND_3") (pintype "passive"))
      (node (ref "U8") (pin "10") (pinfunction "COM_10") (pintype "passive"))
      (node (ref "U8") (pin "21") (pinfunction "PAD_21") (pintype "passive"))
      (node (ref "U8") (pin "4") (pinfunction "GND_4") (pintype "passive"))
      (node (ref "U8") (pin "5") (pinfunction "GND_5") (pintype "passive"))
    )
    (net (code "41") (name "AVCC_3V0") (class "Default")
      (node (ref "C32") (pin "1") (pinfunction "1_1") (pintype "passive"))
      (node (ref "C43") (pin "1") (pinfunction "1_1") (pintype "passive"))
      (node (ref "U7") (pin "2") (pinfunction "OUT_2") (pintype "passive"))
      (node (ref "U8") (pin "2") (pinfunction "REF_2") (pintype "passive"))
    )
    (net (code "42") (name "AVCC_3V3") (class "Default")
      (node (ref "C17") (pin "1") (pinfunction "1_1") (pintype "passive"))
      (node (ref "C31") (pin "1") (pinfunction "1_1") (pintype "passive"))
      (node (ref "C33") (pin "1") (pinfunction "1_1") (pintype "passive"))
      (node (ref "C39") (pin "1") (pinfunction "1_1") (pintype "passive"))
      (node (ref "P5") (pin "2") (pinfunction "2_2") (pintype "passive"))
      (node (ref "U5") (pin "2") (pinfunction "OUT_2") (pintype "passive"))
      (node (ref "U7") (pin "1") (pinfunction "IN_1") (pintype "passive"))
      (node (ref "U8") (pin "1") (pinfunction "VDD_1") (pintype "passive"))
      (node (ref "U8") (pin "20") (pinfunction "VDD_20") (pintype "passive"))
    )
    (net (code "43") (name "AVCC_VBAT") (class "Default")
      (node (ref "C18") (pin "1") (pinfunction "1_1") (pintype "passive"))
      (node (ref "C23") (pin "2") (pinfunction "2_2") (pintype "passive"))
      (node (ref "L6") (pin "2") (pinfunction "2_2") (pintype "passive"))
      (node (ref "U6") (pin "1") (pinfunction "VIN_1") (pintype "passive"))
    )
    (net (code "44") (name "DGND") (class "Default")
      (node (ref "C34") (pin "2") (pinfunction "2_2") (pintype "passive"))
      (node (ref "C35") (pin "2") (pinfunction "2_2") (pintype "passive"))
      (node (ref "C36") (pin "2") (pinfunction "2_2") (pintype "passive"))
      (node (ref "C37") (pin "2") (pinfunction "2_2") (pintype "passive"))
      (node (ref "C38") (pin "1") (pinfunction "1_1") (pintype "passive"))
      (node (ref "C40") (pin "2") (pinfunction "2_2") (pintype "passive"))
      (node (ref "C41") (pin "1") (pinfunction "1_1") (pintype "passive"))
      (node (ref "C42") (pin "1") (pinfunction "1_1") (pintype "passive"))
      (node (ref "C45") (pin "1") (pinfunction "1_1") (pintype "passive"))
      (node (ref "C46") (pin "1") (pinfunction "1_1") (pintype "passive"))
      (node (ref "C47") (pin "2") (pinfunction "2_2") (pintype "passive"))
      (node (ref "C48") (pin "2") (pinfunction "2_2") (pintype "passive"))
      (node (ref "C49") (pin "2") (pinfunction "2_2") (pintype "passive"))
      (node (ref "C50") (pin "1") (pinfunction "1_1") (pintype "passive"))
      (node (ref "C51") (pin "1") (pinfunction "1_1") (pintype "passive"))
      (node (ref "C52") (pin "1") (pinfunction "1_1") (pintype "passive"))
      (node (ref "C59") (pin "1") (pinfunction "1_1") (pintype "passive"))
      (node (ref "C67") (pin "2") (pinfunction "2_2") (pintype "passive"))
      (node (ref "C68") (pin "2") (pinfunction "2_2") (pintype "passive"))
      (node (ref "C70") (pin "2") (pinfunction "2_2") (pintype "passive"))
      (node (ref "C72") (pin "2") (pinfunction "2_2") (pintype "passive"))
      (node (ref "C73") (pin "2") (pinfunction "2_2") (pintype "passive"))
      (node (ref "C74") (pin "2") (pinfunction "2_2") (pintype "passive"))
      (node (ref "C75") (pin "2") (pinfunction "2_2") (pintype "passive"))
      (node (ref "C77") (pin "2") (pinfunction "2_2") (pintype "passive"))
      (node (ref "C79") (pin "2") (pinfunction "2_2") (pintype "passive"))
      (node (ref "D4") (pin "1") (pinfunction "A_1") (pintype "passive"))
      (node (ref "P1") (pin "2") (pinfunction "2_2") (pintype "passive"))
      (node (ref "P4") (pin "5") (pinfunction "5_5") (pintype "passive"))
      (node (ref "Q2") (pin "2") (pinfunction "E_2") (pintype "passive"))
      (node (ref "R10") (pin "2") (pinfunction "2_2") (pintype "passive"))
      (node (ref "R11") (pin "1") (pinfunction "1_1") (pintype "passive"))
      (node (ref "R16") (pin "2") (pinfunction "2_2") (pintype "passive"))
      (node (ref "R17") (pin "2") (pinfunction "2_2") (pintype "passive"))
      (node (ref "R19") (pin "2") (pinfunction "2_2") (pintype "passive"))
      (node (ref "R20") (pin "2") (pinfunction "2_2") (pintype "passive"))
      (node (ref "R29") (pin "1") (pinfunction "1_1") (pintype "passive"))
      (node (ref "R9") (pin "2") (pinfunction "2_2") (pintype "passive"))
      (node (ref "U10") (pin "2") (pinfunction "VSS_2") (pintype "passive"))
      (node (ref "U11") (pin "A1") (pinfunction "VSS_A1") (pintype "passive"))
      (node (ref "U11") (pin "A12") (pinfunction "VSS_A12") (pintype "passive"))
      (node (ref "U11") (pin "A7") (pinfunction "VSS_A7") (pintype "passive"))
      (node (ref "U11") (pin "C1") (pinfunction "VSS_C1") (pintype "passive"))
      (node (ref "U11") (pin "F11") (pinfunction "VSS_F11") (pintype "passive"))
      (node (ref "U11") (pin "G2") (pinfunction "VSS_G2") (pintype "passive"))
      (node (ref "U11") (pin "K1") (pinfunction "VSSA/VREF-_K1") (pintype "passive"))
      (node (ref "U11") (pin "L6") (pinfunction "VSS_L6") (pintype "passive"))
      (node (ref "U11") (pin "M1") (pinfunction "VSS_M1") (pintype "passive"))
      (node (ref "U11") (pin "M12") (pinfunction "VSS_M12") (pintype "passive"))
      (node (ref "U13") (pin "1") (pinfunction "GND_1") (pintype "passive"))
      (node (ref "U9") (pin "2") (pinfunction "GND_2") (pintype "passive"))
      (node (ref "U9") (pin "5") (pinfunction "QOD_5") (pintype "passive"))
    )
    (net (code "45") (name "DVCC_3V3") (class "Default")
      (node (ref "C34") (pin "1") (pinfunction "1_1") (pintype "passive"))
      (node (ref "C38") (pin "2") (pinfunction "2_2") (pintype "passive"))
      (node (ref "C42") (pin "2") (pinfunction "2_2") (pintype "passive"))
      (node (ref "C45") (pin "2") (pinfunction "2_2") (pintype "passive"))
      (node (ref "C46") (pin "2") (pinfunction "2_2") (pintype "passive"))
      (node (ref "C47") (pin "1") (pinfunction "1_1") (pintype "passive"))
      (node (ref "C50") (pin "2") (pinfunction "2_2") (pintype "passive"))
      (node (ref "C51") (pin "2") (pinfunction "2_2") (pintype "passive"))
      (node (ref "C52") (pin "2") (pinfunction "2_2") (pintype "passive"))
      (node (ref "C67") (pin "1") (pinfunction "1_1") (pintype "passive"))
      (node (ref "C68") (pin "1") (pinfunction "1_1") (pintype "passive"))
      (node (ref "C70") (pin "1") (pinfunction "1_1") (pintype "passive"))
      (node (ref "C74") (pin "1") (pinfunction "1_1") (pintype "passive"))
      (node (ref "L7") (pin "2") (pinfunction "2_2") (pintype "passive"))
      (node (ref "L8") (pin "2") (pinfunction "2_2") (pintype "passive"))
      (node (ref "P1") (pin "1") (pinfunction "1_1") (pintype "passive"))
      (node (ref "P4") (pin "1") (pinfunction "1_1") (pintype "passive"))
      (node (ref "R18") (pin "1") (pinfunction "1_1") (pintype "passive"))
      (node (ref "R21") (pin "1") (pinfunction "1_1") (pintype "passive"))
      (node (ref "U11") (pin "A11") (pinfunction "VDD_A11") (pintype "passive"))
      (node (ref "U11") (pin "A6") (pinfunction "VDDIO2_A6") (pintype "passive"))
      (node (ref "U11") (pin "B2") (pinfunction "VDD_B2") (pintype "passive"))
      (node (ref "U11") (pin "E12") (pinfunction "VDDIO2_E12") (pintype "passive"))
      (node (ref "U11") (pin "G1") (pinfunction "VDD_G1") (pintype "passive"))
      (node (ref "U11") (pin "G12") (pinfunction "VDD_G12") (pintype "passive"))
      (node (ref "U11") (pin "K2") (pinfunction "VREF+_K2") (pintype "passive"))
      (node (ref "U11") (pin "L11") (pinfunction "VDD_L11") (pintype "passive"))
      (node (ref "U11") (pin "M2") (pinfunction "VDD_M2") (pintype "passive"))
      (node (ref "U11") (pin "M6") (pinfunction "VDD_M6") (pintype "passive"))
      (node (ref "U13") (pin "2") (pinfunction "OUT_2") (pintype "passive"))
      (node (ref "U8") (pin "15") (pinfunction "VIO_15") (pintype "passive"))
    )
    (net (code "46") (name "ESP32_GND") (class "Default")
      (node (ref "C1") (pin "2") (pinfunction "2_2") (pintype "passive"))
      (node (ref "C2") (pin "2") (pinfunction "2_2") (pintype "passive"))
      (node (ref "C26") (pin "2") (pinfunction "2_2") (pintype "passive"))
      (node (ref "C27") (pin "2") (pinfunction "2_2") (pintype "passive"))
      (node (ref "C28") (pin "2") (pintype "passive"))
      (node (ref "C29") (pin "2") (pintype "passive"))
      (node (ref "C3") (pin "2") (pinfunction "2_2") (pintype "passive"))
      (node (ref "C4") (pin "2") (pinfunction "2_2") (pintype "passive"))
      (node (ref "C5") (pin "2") (pinfunction "2_2") (pintype "passive"))
      (node (ref "P2") (pin "4") (pinfunction "4_4") (pintype "passive"))
      (node (ref "P3") (pin "2") (pinfunction "2_2") (pintype "passive"))
      (node (ref "P3") (pin "3") (pinfunction "3_3") (pintype "passive"))
      (node (ref "R12") (pin "1") (pinfunction "1_1") (pintype "passive"))
      (node (ref "R3") (pin "2") (pinfunction "2_2") (pintype "passive"))
      (node (ref "U1") (pin "2") (pinfunction "GND_2") (pintype "passive"))
      (node (ref "U1") (pin "5") (pinfunction "QOD_5") (pintype "passive"))
      (node (ref "U2") (pin "2") (pinfunction "GND_2") (pintype "passive"))
      (node (ref "U3") (pin "1") (pinfunction "GND_1") (pintype "passive"))
      (node (ref "U3") (pin "10") (pinfunction "GND_10") (pintype "passive"))
      (node (ref "U3") (pin "15") (pinfunction "GND_15") (pintype "passive"))
      (node (ref "U3") (pin "23") (pinfunction "GND_23") (pintype "passive"))
      (node (ref "U3") (pin "29") (pinfunction "GND_29") (pintype "passive"))
      (node (ref "U3") (pin "31") (pinfunction "GND_31") (pintype "passive"))
      (node (ref "U3") (pin "7") (pinfunction "GND_7") (pintype "passive"))
    )
    (net (code "47") (name "ESP32_VCC") (class "Default")
      (node (ref "C26") (pin "1") (pinfunction "1_1") (pintype "passive"))
      (node (ref "C27") (pin "1") (pinfunction "1_1") (pintype "passive"))
      (node (ref "C5") (pin "1") (pinfunction "1_1") (pintype "passive"))
      (node (ref "R2") (pin "1") (pinfunction "1_1") (pintype "passive"))
      (node (ref "R4") (pin "1") (pinfunction "1_1") (pintype "passive"))
      (node (ref "U2") (pin "5") (pinfunction "VOUT_5") (pintype "passive"))
      (node (ref "U3") (pin "6") (pinfunction "VCC_3V3_6") (pintype "passive"))
    )
    (net (code "48") (name "ESP_VBAT") (class "Default")
      (node (ref "C35") (pin "1") (pinfunction "1_1") (pintype "passive"))
      (node (ref "C44") (pin "2") (pinfunction "2_2") (pintype "passive"))
      (node (ref "R15") (pin "2") (pinfunction "2_2") (pintype "passive"))
      (node (ref "U9") (pin "1") (pinfunction "VIN_1") (pintype "passive"))
    )
    (net (code "49") (name "LMT+3V0") (class "Default")
      (node (ref "C37") (pin "1") (pinfunction "1_1") (pintype "passive"))
      (node (ref "D4") (pin "2") (pinfunction "K_2") (pintype "passive"))
      (node (ref "P5") (pin "8") (pinfunction "8_8") (pintype "passive"))
      (node (ref "R14") (pin "1") (pinfunction "1_1") (pintype "passive"))
      (node (ref "U10") (pin "5") (pinfunction "VOUT_5") (pintype "passive"))
    )
    (net (code "50") (name "Net-(C21-Pad1)") (class "Default")
      (node (ref "C21") (pin "1") (pinfunction "1_1") (pintype "passive"))
      (node (ref "L5") (pin "2") (pinfunction "2_2") (pintype "passive"))
      (node (ref "L6") (pin "1") (pinfunction "1_1") (pintype "passive"))
    )
    (net (code "51") (name "Net-(C28-Pad1)") (class "Default")
      (node (ref "C28") (pin "1") (pintype "passive"))
      (node (ref "P3") (pin "1") (pinfunction "1_1") (pintype "passive"))
      (node (ref "R13") (pin "2") (pinfunction "2_2") (pintype "passive"))
    )
    (net (code "52") (name "Net-(D2-K)") (class "Default")
      (node (ref "D2") (pin "2") (pinfunction "K_2") (pintype "passive"))
      (node (ref "R9") (pin "1") (pinfunction "1_1") (pintype "passive"))
    )
    (net (code "53") (name "Net-(EGND1-Pad0)") (class "Default")
      (node (ref "EGND1") (pin "0") (pinfunction "0_0") (pintype "passive"))
      (node (ref "EGND2") (pin "0") (pinfunction "0_0") (pintype "passive"))
      (node (ref "EGND3") (pin "0") (pinfunction "0_0") (pintype "passive"))
      (node (ref "EGND4") (pin "0") (pinfunction "0_0") (pintype "passive"))
    )
    (net (code "54") (name "Net-(U1-CT)") (class "Default")
      (node (ref "C13") (pin "1") (pinfunction "1_1") (pintype "passive"))
      (node (ref "U1") (pin "4") (pinfunction "CT_4") (pintype "passive"))
    )
    (net (code "55") (name "Net-(U1-VOUT)") (class "Default")
      (node (ref "C3") (pin "1") (pinfunction "1_1") (pintype "passive"))
      (node (ref "U1") (pin "6") (pinfunction "VOUT_6") (pintype "passive"))
      (node (ref "U2") (pin "1") (pinfunction "VIN_1") (pintype "passive"))
      (node (ref "U2") (pin "3") (pinfunction "EN_3") (pintype "passive"))
    )
    (net (code "56") (name "Net-(U2-BYP)") (class "Default")
      (node (ref "C4") (pin "1") (pinfunction "1_1") (pintype "passive"))
      (node (ref "U2") (pin "4") (pinfunction "BYP_4") (pintype "passive"))
    )
    (net (code "57") (name "Net-(U5-VIN)") (class "Default")
      (node (ref "C19") (pin "1") (pinfunction "1_1") (pintype "passive"))
      (node (ref "C20") (pin "1") (pinfunction "1_1") (pintype "passive"))
      (node (ref "U5") (pin "3") (pinfunction "VIN_3") (pintype "passive"))
      (node (ref "U6") (pin "6") (pinfunction "VOUT_6") (pintype "passive"))
    )
    (net (code "58") (name "Net-(U6-CT)") (class "Default")
      (node (ref "C23") (pin "1") (pinfunction "1_1") (pintype "passive"))
      (node (ref "U6") (pin "4") (pinfunction "CT_4") (pintype "passive"))
    )
    (net (code "59") (name "Net-(U9-CT)") (class "Default")
      (node (ref "C44") (pin "1") (pinfunction "1_1") (pintype "passive"))
      (node (ref "U9") (pin "4") (pinfunction "CT_4") (pintype "passive"))
    )
    (net (code "60") (name "Net-(U10-CE)") (class "Default")
      (node (ref "C36") (pin "1") (pinfunction "1_1") (pintype "passive"))
      (node (ref "U10") (pin "1") (pinfunction "VIN_1") (pintype "passive"))
      (node (ref "U10") (pin "3") (pinfunction "CE_3") (pintype "passive"))
      (node (ref "U9") (pin "6") (pinfunction "VOUT_6") (pintype "passive"))
    )
    (net (code "61") (name "Net-(U11-DSI_D0N)") (class "Default")
      (node (ref "R19") (pin "1") (pinfunction "1_1") (pintype "passive"))
      (node (ref "U11") (pin "K12") (pinfunction "DSI_D0N_K12") (pintype "passive"))
    )
    (net (code "62") (name "Net-(U11-DSI_D0P)") (class "Default")
      (node (ref "R20") (pin "1") (pinfunction "1_1") (pintype "passive"))
      (node (ref "U11") (pin "K11") (pinfunction "DSI_D0P_K11") (pintype "passive"))
    )
    (net (code "63") (name "Net-(U11-PH3-BOOT0)") (class "Default")
      (node (ref "R29") (pin "2") (pinfunction "2_2") (pintype "passive"))
      (node (ref "U11") (pin "A4") (pinfunction "PH3-BOOT0_A4") (pintype "passive"))
    )
    (net (code "64") (name "Net-(U11-VBAT)") (class "Default")
      (node (ref "R18") (pin "2") (pinfunction "2_2") (pintype "passive"))
      (node (ref "U11") (pin "B1") (pinfunction "VBAT_B1") (pintype "passive"))
    )
    (net (code "65") (name "Net-(U11-VDDA)") (class "Default")
      (node (ref "C40") (pin "1") (pinfunction "1_1") (pintype "passive"))
      (node (ref "C41") (pin "2") (pinfunction "2_2") (pintype "passive"))
      (node (ref "L7") (pin "1") (pinfunction "1_1") (pintype "passive"))
      (node (ref "U11") (pin "L1") (pinfunction "VDDA_L1") (pintype "passive"))
    )
    (net (code "66") (name "Net-(U11-VDDUSB)") (class "Default")
      (node (ref "C48") (pin "1") (pinfunction "1_1") (pintype "passive"))
      (node (ref "C49") (pin "1") (pinfunction "1_1") (pintype "passive"))
      (node (ref "L8") (pin "1") (pinfunction "1_1") (pintype "passive"))
      (node (ref "U11") (pin "C11") (pinfunction "VDDUSB_C11") (pintype "passive"))
    )
    (net (code "67") (name "Net-(U13-VIN)") (class "Default")
      (node (ref "C75") (pin "1") (pinfunction "1_1") (pintype "passive"))
      (node (ref "L9") (pin "2") (pinfunction "2_2") (pintype "passive"))
      (node (ref "U13") (pin "3") (pinfunction "VIN_3") (pintype "passive"))
    )
    (net (code "68") (name "VBAT_GND") (class "Default")
      (node (ref "BT1") (pin "2") (pinfunction "-_2") (pintype "passive"))
      (node (ref "C11") (pin "1") (pinfunction "1_1") (pintype "passive"))
      (node (ref "C12") (pin "1") (pinfunction "1_1") (pintype "passive"))
      (node (ref "R11") (pin "2") (pinfunction "2_2") (pintype "passive"))
      (node (ref "R12") (pin "2") (pinfunction "2_2") (pintype "passive"))
    )
    (net (code "69") (name "VBAT_POWER") (class "Default")
      (node (ref "BT1") (pin "1") (pinfunction "+_1") (pintype "passive"))
      (node (ref "C11") (pin "2") (pinfunction "2_2") (pintype "passive"))
      (node (ref "C12") (pin "2") (pinfunction "2_2") (pintype "passive"))
      (node (ref "C22") (pin "1") (pinfunction "1_1") (pintype "passive"))
      (node (ref "L5") (pin "1") (pinfunction "1_1") (pintype "passive"))
      (node (ref "L9") (pin "1") (pinfunction "1_1") (pintype "passive"))
      (node (ref "R1") (pin "1") (pinfunction "1_1") (pintype "passive"))
      (node (ref "R15") (pin "1") (pinfunction "1_1") (pintype "passive"))
    )
    (net (code "70") (name "V_POWER") (class "Default")
      (node (ref "C1") (pin "1") (pinfunction "1_1") (pintype "passive"))
      (node (ref "C13") (pin "2") (pinfunction "2_2") (pintype "passive"))
      (node (ref "C2") (pin "1") (pinfunction "1_1") (pintype "passive"))
      (node (ref "R1") (pin "2") (pinfunction "2_2") (pintype "passive"))
      (node (ref "U1") (pin "1") (pinfunction "VIN_1") (pintype "passive"))
    )
    (net (code "71") (name "unconnected-(U3-ADC5-Pad11)") (class "Default")
      (node (ref "U3") (pin "11") (pinfunction "ADC5_11") (pintype "passive"))
    )
    (net (code "72") (name "unconnected-(U3-ADC6-Pad12)") (class "Default")
      (node (ref "U3") (pin "12") (pinfunction "ADC6_12") (pintype "passive"))
    )
    (net (code "73") (name "unconnected-(U3-ADC7-Pad13)") (class "Default")
      (node (ref "U3") (pin "13") (pinfunction "ADC7_13") (pintype "passive"))
    )
    (net (code "74") (name "unconnected-(U3-ADC8-Pad14)") (class "Default")
      (node (ref "U3") (pin "14") (pinfunction "ADC8_14") (pintype "passive"))
    )
    (net (code "75") (name "unconnected-(U3-BOOT0-Pad26)") (class "Default")
      (node (ref "U3") (pin "26") (pinfunction "BOOT0_26") (pintype "passive"))
    )
    (net (code "76") (name "unconnected-(U3-EXTI_PULSE-Pad16)") (class "Default")
      (node (ref "U3") (pin "16") (pinfunction "EXTI_PULSE_16") (pintype "passive"))
    )
    (net (code "77") (name "unconnected-(U3-I2C1_SCL-Pad27)") (class "Default")
      (node (ref "U3") (pin "27") (pinfunction "I2C1_SCL_27") (pintype "passive"))
    )
    (net (code "78") (name "unconnected-(U3-I2C1_SDA-Pad28)") (class "Default")
      (node (ref "U3") (pin "28") (pinfunction "I2C1_SDA_28") (pintype "passive"))
    )
    (net (code "79") (name "unconnected-(U3-PWM_OUT-Pad20)") (class "Default")
      (node (ref "U3") (pin "20") (pinfunction "PWM_OUT_20") (pintype "passive"))
    )
    (net (code "80") (name "unconnected-(U3-SWITCH_IN-Pad21)") (class "Default")
      (node (ref "U3") (pin "21") (pinfunction "SWITCH_IN_21") (pintype "passive"))
    )
    (net (code "81") (name "unconnected-(U3-SWITCH_OUT-Pad22)") (class "Default")
      (node (ref "U3") (pin "22") (pinfunction "SWITCH_OUT_22") (pintype "passive"))
    )
    (net (code "82") (name "unconnected-(U3-SYSTEM_WAK__E_UP-Pad2)") (class "Default")
      (node (ref "U3") (pin "2") (pinfunction "SYSTEM_WAK__E_UP_2") (pintype "passive"))
    )
    (net (code "83") (name "unconnected-(U3-UART2_CTS-Pad3)") (class "Default")
      (node (ref "U3") (pin "3") (pinfunction "UART2_CTS_3") (pintype "passive"))
    )
    (net (code "84") (name "unconnected-(U3-UART2_RTS-Pad4)") (class "Default")
      (node (ref "U3") (pin "4") (pinfunction "UART2_RTS_4") (pintype "passive"))
    )
    (net (code "85") (name "unconnected-(U3-UART2_RX-Pad9)") (class "Default")
      (node (ref "U3") (pin "9") (pinfunction "UART2_RX_9") (pintype "passive"))
    )
    (net (code "86") (name "unconnected-(U3-UART2_TX-Pad8)") (class "Default")
      (node (ref "U3") (pin "8") (pinfunction "UART2_TX_8") (pintype "passive"))
    )
    (net (code "87") (name "unconnected-(U8-NC-Pad6)") (class "Default")
      (node (ref "U8") (pin "6") (pinfunction "NC_6") (pintype "passive+no_connect"))
    )
    (net (code "88") (name "unconnected-(U8-NC-Pad8)") (class "Default")
      (node (ref "U8") (pin "8") (pinfunction "NC_8") (pintype "passive+no_connect"))
    )
    (net (code "89") (name "unconnected-(U8-NC-Pad17)") (class "Default")
      (node (ref "U8") (pin "17") (pinfunction "NC_17") (pintype "passive+no_connect"))
    )
    (net (code "90") (name "unconnected-(U8-NC-Pad19)") (class "Default")
      (node (ref "U8") (pin "19") (pinfunction "NC_19") (pintype "passive+no_connect"))
    )
    (net (code "91") (name "unconnected-(U8-REFIN-Pad3)") (class "Default")
      (node (ref "U8") (pin "3") (pinfunction "REFIN_3") (pintype "passive+no_connect"))
    )
    (net (code "92") (name "unconnected-(U10-NC-Pad4)") (class "Default")
      (node (ref "U10") (pin "4") (pinfunction "NC_4") (pintype "passive"))
    )
    (net (code "93") (name "unconnected-(U11-DSI_CKN-PadJ12)") (class "Default")
      (node (ref "U11") (pin "J12") (pinfunction "DSI_CKN_J12") (pintype "passive"))
    )
    (net (code "94") (name "unconnected-(U11-DSI_CKP-PadJ11)") (class "Default")
      (node (ref "U11") (pin "J11") (pinfunction "DSI_CKP_J11") (pintype "passive"))
    )
    (net (code "95") (name "unconnected-(U11-DSI_D1N-PadH12)") (class "Default")
      (node (ref "U11") (pin "H12") (pinfunction "DSI_D1N_H12") (pintype "passive"))
    )
    (net (code "96") (name "unconnected-(U11-DSI_D1P-PadH11)") (class "Default")
      (node (ref "U11") (pin "H11") (pinfunction "DSI_D1P_H11") (pintype "passive"))
    )
    (net (code "97") (name "unconnected-(U11-PA0-PadK3)") (class "Default")
      (node (ref "U11") (pin "K3") (pinfunction "PA0_K3") (pintype "passive"))
    )
    (net (code "98") (name "unconnected-(U11-PA1-PadL2)") (class "Default")
      (node (ref "U11") (pin "L2") (pinfunction "PA1_L2") (pintype "passive"))
    )
    (net (code "99") (name "unconnected-(U11-PA2-PadL3)") (class "Default")
      (node (ref "U11") (pin "L3") (pinfunction "PA2_L3") (pintype "passive"))
    )
    (net (code "100") (name "unconnected-(U11-PA8-PadD11)") (class "Default")
      (node (ref "U11") (pin "D11") (pinfunction "PA8_D11") (pintype "passive"))
    )
    (net (code "101") (name "unconnected-(U11-PA11-PadB12)") (class "Default")
      (node (ref "U11") (pin "B12") (pinfunction "PA11_B12") (pintype "passive"))
    )
    (net (code "102") (name "unconnected-(U11-PA12-PadB11)") (class "Default")
      (node (ref "U11") (pin "B11") (pinfunction "PA12_B11") (pintype "passive"))
    )
    (net (code "103") (name "unconnected-(U11-PB1-PadJ5)") (class "Default")
      (node (ref "U11") (pin "J5") (pinfunction "PB1_J5") (pintype "passive"))
    )
    (net (code "104") (name "unconnected-(U11-PB2-PadH5)") (class "Default")
      (node (ref "U11") (pin "H5") (pinfunction "PB2_H5") (pintype "passive"))
    )
    (net (code "105") (name "unconnected-(U11-PB5-PadB5)") (class "Default")
      (node (ref "U11") (pin "B5") (pinfunction "PB5_B5") (pintype "passive"))
    )
    (net (code "106") (name "unconnected-(U11-PB6-PadD5)") (class "Default")
      (node (ref "U11") (pin "D5") (pinfunction "PB6_D5") (pintype "passive"))
    )
    (net (code "107") (name "unconnected-(U11-PB7-PadC5)") (class "Default")
      (node (ref "U11") (pin "C5") (pinfunction "PB7_C5") (pintype "passive"))
    )
    (net (code "108") (name "unconnected-(U11-PB8-PadB4)") (class "Default")
      (node (ref "U11") (pin "B4") (pinfunction "PB8_B4") (pintype "passive"))
    )
    (net (code "109") (name "unconnected-(U11-PB9-PadA3)") (class "Default")
      (node (ref "U11") (pin "A3") (pinfunction "PB9_A3") (pintype "passive"))
    )
    (net (code "110") (name "unconnected-(U11-PB11-PadK9)") (class "Default")
      (node (ref "U11") (pin "K9") (pinfunction "PB11_K9") (pintype "passive"))
    )
    (net (code "111") (name "unconnected-(U11-PB15-PadJ9)") (class "Default")
      (node (ref "U11") (pin "J9") (pinfunction "PB15_J9") (pintype "passive"))
    )
    (net (code "112") (name "unconnected-(U11-PC0-PadH3)") (class "Default")
      (node (ref "U11") (pin "H3") (pinfunction "PC0_H3") (pintype "passive"))
    )
    (net (code "113") (name "unconnected-(U11-PC1-PadJ2)") (class "Default")
      (node (ref "U11") (pin "J2") (pinfunction "PC1_J2") (pintype "passive"))
    )
    (net (code "114") (name "unconnected-(U11-PC2-PadH4)") (class "Default")
      (node (ref "U11") (pin "H4") (pinfunction "PC2_H4") (pintype "passive"))
    )
    (net (code "115") (name "unconnected-(U11-PC3-PadJ3)") (class "Default")
      (node (ref "U11") (pin "J3") (pinfunction "PC3_J3") (pintype "passive"))
    )
    (net (code "116") (name "unconnected-(U11-PC4-PadL5)") (class "Default")
      (node (ref "U11") (pin "L5") (pinfunction "PC4_L5") (pintype "passive"))
    )
    (net (code "117") (name "unconnected-(U11-PC7-PadE9)") (class "Default")
      (node (ref "U11") (pin "E9") (pinfunction "PC7_E9") (pintype "passive"))
    )
    (net (code "118") (name "unconnected-(U11-PC8-PadE10)") (class "Default")
      (node (ref "U11") (pin "E10") (pinfunction "PC8_E10") (pintype "passive"))
    )
    (net (code "119") (name "unconnected-(U11-PC9-PadC12)") (class "Default")
      (node (ref "U11") (pin "C12") (pinfunction "PC9_C12") (pintype "passive"))
    )
    (net (code "120") (name "unconnected-(U11-PC10-PadC9)") (class "Default")
      (node (ref "U11") (pin "C9") (pinfunction "PC10_C9") (pintype "passive"))
    )
    (net (code "121") (name "unconnected-(U11-PC11-PadA9)") (class "Default")
      (node (ref "U11") (pin "A9") (pinfunction "PC11_A9") (pintype "passive"))
    )
    (net (code "122") (name "unconnected-(U11-PC12-PadD9)") (class "Default")
      (node (ref "U11") (pin "D9") (pinfunction "PC12_D9") (pintype "passive"))
    )
    (net (code "123") (name "unconnected-(U11-PC13-PadE4)") (class "Default")
      (node (ref "U11") (pin "E4") (pinfunction "PC13_E4") (pintype "passive"))
    )
    (net (code "124") (name "unconnected-(U11-PD0-PadC8)") (class "Default")
      (node (ref "U11") (pin "C8") (pinfunction "PD0_C8") (pintype "passive"))
    )
    (net (code "125") (name "unconnected-(U11-PD1-PadB8)") (class "Default")
      (node (ref "U11") (pin "B8") (pinfunction "PD1_B8") (pintype "passive"))
    )
    (net (code "126") (name "unconnected-(U11-PD2-PadD8)") (class "Default")
      (node (ref "U11") (pin "D8") (pinfunction "PD2_D8") (pintype "passive"))
    )
    (net (code "127") (name "unconnected-(U11-PD3-PadA8)") (class "Default")
      (node (ref "U11") (pin "A8") (pinfunction "PD3_A8") (pintype "passive"))
    )
    (net (code "128") (name "unconnected-(U11-PD4-PadC7)") (class "Default")
      (node (ref "U11") (pin "C7") (pinfunction "PD4_C7") (pintype "passive"))
    )
    (net (code "129") (name "unconnected-(U11-PD6-PadB7)") (class "Default")
      (node (ref "U11") (pin "B7") (pinfunction "PD6_B7") (pintype "passive"))
    )
    (net (code "130") (name "unconnected-(U11-PD7-PadE7)") (class "Default")
      (node (ref "U11") (pin "E7") (pinfunction "PD7_E7") (pintype "passive"))
    )
    (net (code "131") (name "unconnected-(U11-PD8-PadH10)") (class "Default")
      (node (ref "U11") (pin "H10") (pinfunction "PD8_H10") (pintype "passive"))
    )
    (net (code "132") (name "unconnected-(U11-PD9-PadH9)") (class "Default")
      (node (ref "U11") (pin "H9") (pinfunction "PD9_H9") (pintype "passive"))
    )
    (net (code "133") (name "unconnected-(U11-PD10-PadH8)") (class "Default")
      (node (ref "U11") (pin "H8") (pinfunction "PD10_H8") (pintype "passive"))
    )
    (net (code "134") (name "unconnected-(U11-PD12-PadG9)") (class "Default")
      (node (ref "U11") (pin "G9") (pinfunction "PD12_G9") (pintype "passive"))
    )
    (net (code "135") (name "unconnected-(U11-PD13-PadG10)") (class "Default")
      (node (ref "U11") (pin "G10") (pinfunction "PD13_G10") (pintype "passive"))
    )
    (net (code "136") (name "unconnected-(U11-PD14-PadG8)") (class "Default")
      (node (ref "U11") (pin "G8") (pinfunction "PD14_G8") (pintype "passive"))
    )
    (net (code "137") (name "unconnected-(U11-PD15-PadG7)") (class "Default")
      (node (ref "U11") (pin "G7") (pinfunction "PD15_G7") (pintype "passive"))
    )
    (net (code "138") (name "unconnected-(U11-PE1-PadC4)") (class "Default")
      (node (ref "U11") (pin "C4") (pinfunction "PE1_C4") (pintype "passive"))
    )
    (net (code "139") (name "unconnected-(U11-PE2-PadC3)") (class "Default")
      (node (ref "U11") (pin "C3") (pinfunction "PE2_C3") (pintype "passive"))
    )
    (net (code "140") (name "unconnected-(U11-PE3-PadB3)") (class "Default")
      (node (ref "U11") (pin "B3") (pinfunction "PE3_B3") (pintype "passive"))
    )
    (net (code "141") (name "unconnected-(U11-PE4-PadD3)") (class "Default")
      (node (ref "U11") (pin "D3") (pinfunction "PE4_D3") (pintype "passive"))
    )
    (net (code "142") (name "unconnected-(U11-PE5-PadC2)") (class "Default")
      (node (ref "U11") (pin "C2") (pinfunction "PE5_C2") (pintype "passive"))
    )
    (net (code "143") (name "unconnected-(U11-PE6-PadD4)") (class "Default")
      (node (ref "U11") (pin "D4") (pinfunction "PE6_D4") (pintype "passive"))
    )
    (net (code "144") (name "unconnected-(U11-PE7-PadG6)") (class "Default")
      (node (ref "U11") (pin "G6") (pinfunction "PE7_G6") (pintype "passive"))
    )
    (net (code "145") (name "unconnected-(U11-PE8-PadK7)") (class "Default")
      (node (ref "U11") (pin "K7") (pinfunction "PE8_K7") (pintype "passive"))
    )
    (net (code "146") (name "unconnected-(U11-PE9-PadJ7)") (class "Default")
      (node (ref "U11") (pin "J7") (pinfunction "PE9_J7") (pintype "passive"))
    )
    (net (code "147") (name "unconnected-(U11-PE10-PadL8)") (class "Default")
      (node (ref "U11") (pin "L8") (pinfunction "PE10_L8") (pintype "passive"))
    )
    (net (code "148") (name "unconnected-(U11-PE11-PadH7)") (class "Default")
      (node (ref "U11") (pin "H7") (pinfunction "PE11_H7") (pintype "passive"))
    )
    (net (code "149") (name "unconnected-(U11-PE13-PadJ8)") (class "Default")
      (node (ref "U11") (pin "J8") (pinfunction "PE13_J8") (pintype "passive"))
    )
    (net (code "150") (name "unconnected-(U11-PE15-PadK8)") (class "Default")
      (node (ref "U11") (pin "K8") (pinfunction "PE15_K8") (pintype "passive"))
    )
    (net (code "151") (name "unconnected-(U11-PF0-PadE3)") (class "Default")
      (node (ref "U11") (pin "E3") (pinfunction "PF0_E3") (pintype "passive"))
    )
    (net (code "152") (name "unconnected-(U11-PF1-PadE2)") (class "Default")
      (node (ref "U11") (pin "E2") (pinfunction "PF1_E2") (pintype "passive"))
    )
    (net (code "153") (name "unconnected-(U11-PF2-PadE1)") (class "Default")
      (node (ref "U11") (pin "E1") (pinfunction "PF2_E1") (pintype "passive"))
    )
    (net (code "154") (name "unconnected-(U11-PF3-PadE5)") (class "Default")
      (node (ref "U11") (pin "E5") (pinfunction "PF3_E5") (pintype "passive"))
    )
    (net (code "155") (name "unconnected-(U11-PF4-PadF3)") (class "Default")
      (node (ref "U11") (pin "F3") (pinfunction "PF4_F3") (pintype "passive"))
    )
    (net (code "156") (name "unconnected-(U11-PF5-PadF4)") (class "Default")
      (node (ref "U11") (pin "F4") (pinfunction "PF5_F4") (pintype "passive"))
    )
    (net (code "157") (name "unconnected-(U11-PF6-PadF2)") (class "Default")
      (node (ref "U11") (pin "F2") (pinfunction "PF6_F2") (pintype "passive"))
    )
    (net (code "158") (name "unconnected-(U11-PF7-PadF5)") (class "Default")
      (node (ref "U11") (pin "F5") (pinfunction "PF7_F5") (pintype "passive"))
    )
    (net (code "159") (name "unconnected-(U11-PF8-PadF1)") (class "Default")
      (node (ref "U11") (pin "F1") (pinfunction "PF8_F1") (pintype "passive"))
    )
    (net (code "160") (name "unconnected-(U11-PF9-PadG4)") (class "Default")
      (node (ref "U11") (pin "G4") (pinfunction "PF9_G4") (pintype "passive"))
    )
    (net (code "161") (name "unconnected-(U11-PF10-PadG3)") (class "Default")
      (node (ref "U11") (pin "G3") (pinfunction "PF10_G3") (pintype "passive"))
    )
    (net (code "162") (name "unconnected-(U11-PF11-PadK6)") (class "Default")
      (node (ref "U11") (pin "K6") (pinfunction "PF11_K6") (pintype "passive"))
    )
    (net (code "163") (name "unconnected-(U11-PF12-PadG5)") (class "Default")
      (node (ref "U11") (pin "G5") (pinfunction "PF12_G5") (pintype "passive"))
    )
    (net (code "164") (name "unconnected-(U11-PF13-PadJ6)") (class "Default")
      (node (ref "U11") (pin "J6") (pinfunction "PF13_J6") (pintype "passive"))
    )
    (net (code "165") (name "unconnected-(U11-PF14-PadM7)") (class "Default")
      (node (ref "U11") (pin "M7") (pinfunction "PF14_M7") (pintype "passive"))
    )
    (net (code "166") (name "unconnected-(U11-PF15-PadH6)") (class "Default")
      (node (ref "U11") (pin "H6") (pinfunction "PF15_H6") (pintype "passive"))
    )
    (net (code "167") (name "unconnected-(U11-PG0-PadL7)") (class "Default")
      (node (ref "U11") (pin "L7") (pinfunction "PG0_L7") (pintype "passive"))
    )
    (net (code "168") (name "unconnected-(U11-PG1-PadM8)") (class "Default")
      (node (ref "U11") (pin "M8") (pinfunction "PG1_M8") (pintype "passive"))
    )
    (net (code "169") (name "unconnected-(U11-PG2-PadF12)") (class "Default")
      (node (ref "U11") (pin "F12") (pinfunction "PG2_F12") (pintype "passive"))
    )
    (net (code "170") (name "unconnected-(U11-PG3-PadF7)") (class "Default")
      (node (ref "U11") (pin "F7") (pinfunction "PG3_F7") (pintype "passive"))
    )
    (net (code "171") (name "unconnected-(U11-PG4-PadF10)") (class "Default")
      (node (ref "U11") (pin "F10") (pinfunction "PG4_F10") (pintype "passive"))
    )
    (net (code "172") (name "unconnected-(U11-PG5-PadF8)") (class "Default")
      (node (ref "U11") (pin "F8") (pinfunction "PG5_F8") (pintype "passive"))
    )
    (net (code "173") (name "unconnected-(U11-PG6-PadF9)") (class "Default")
      (node (ref "U11") (pin "F9") (pinfunction "PG6_F9") (pintype "passive"))
    )
    (net (code "174") (name "unconnected-(U11-PG7-PadE11)") (class "Default")
      (node (ref "U11") (pin "E11") (pinfunction "PG7_E11") (pintype "passive"))
    )
    (net (code "175") (name "unconnected-(U11-PG8-PadE8)") (class "Default")
      (node (ref "U11") (pin "E8") (pinfunction "PG8_E8") (pintype "passive"))
    )
    (net (code "176") (name "unconnected-(U11-PG9-PadF6)") (class "Default")
      (node (ref "U11") (pin "F6") (pinfunction "PG9_F6") (pintype "passive"))
    )
    (net (code "177") (name "unconnected-(U11-PG10-PadE6)") (class "Default")
      (node (ref "U11") (pin "E6") (pinfunction "PG10_E6") (pintype "passive"))
    )
    (net (code "178") (name "unconnected-(U11-PG12-PadD6)") (class "Default")
      (node (ref "U11") (pin "D6") (pinfunction "PG12_D6") (pintype "passive"))
    )
    (net (code "179") (name "unconnected-(U11-PG13-PadC6)") (class "Default")
      (node (ref "U11") (pin "C6") (pinfunction "PG13_C6") (pintype "passive"))
    )
    (net (code "180") (name "unconnected-(U11-VCAPDSI-PadL12)") (class "Default")
      (node (ref "U11") (pin "L12") (pinfunction "VCAPDSI_L12") (pintype "passive"))
    )
    (net (code "181") (name "unconnected-(U11-VSSDSI-PadJ10)") (class "Default")
      (node (ref "U11") (pin "J10") (pinfunction "VSSDSI_J10") (pintype "passive"))
    )
  )
)
